# controller.net
KiCad netlist of a schematic drawn in EAGLE
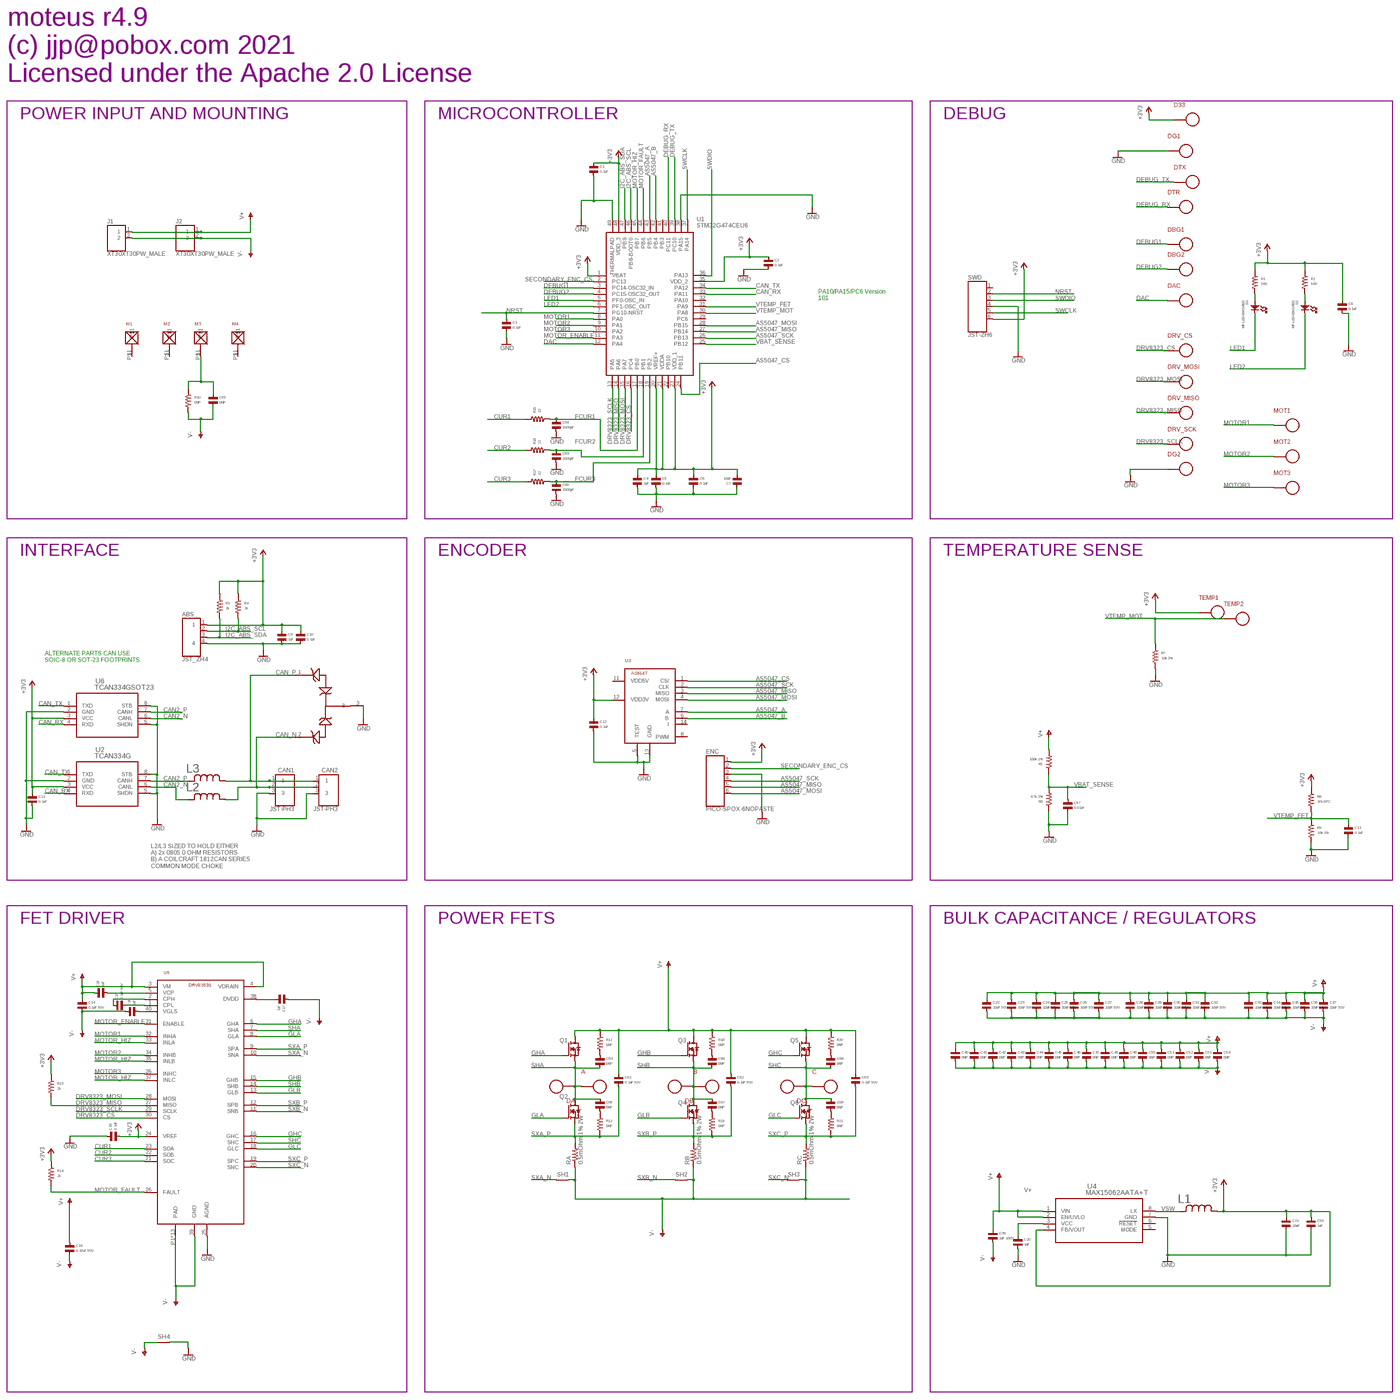
[diagram p0: schematic, sheet 1, overview]
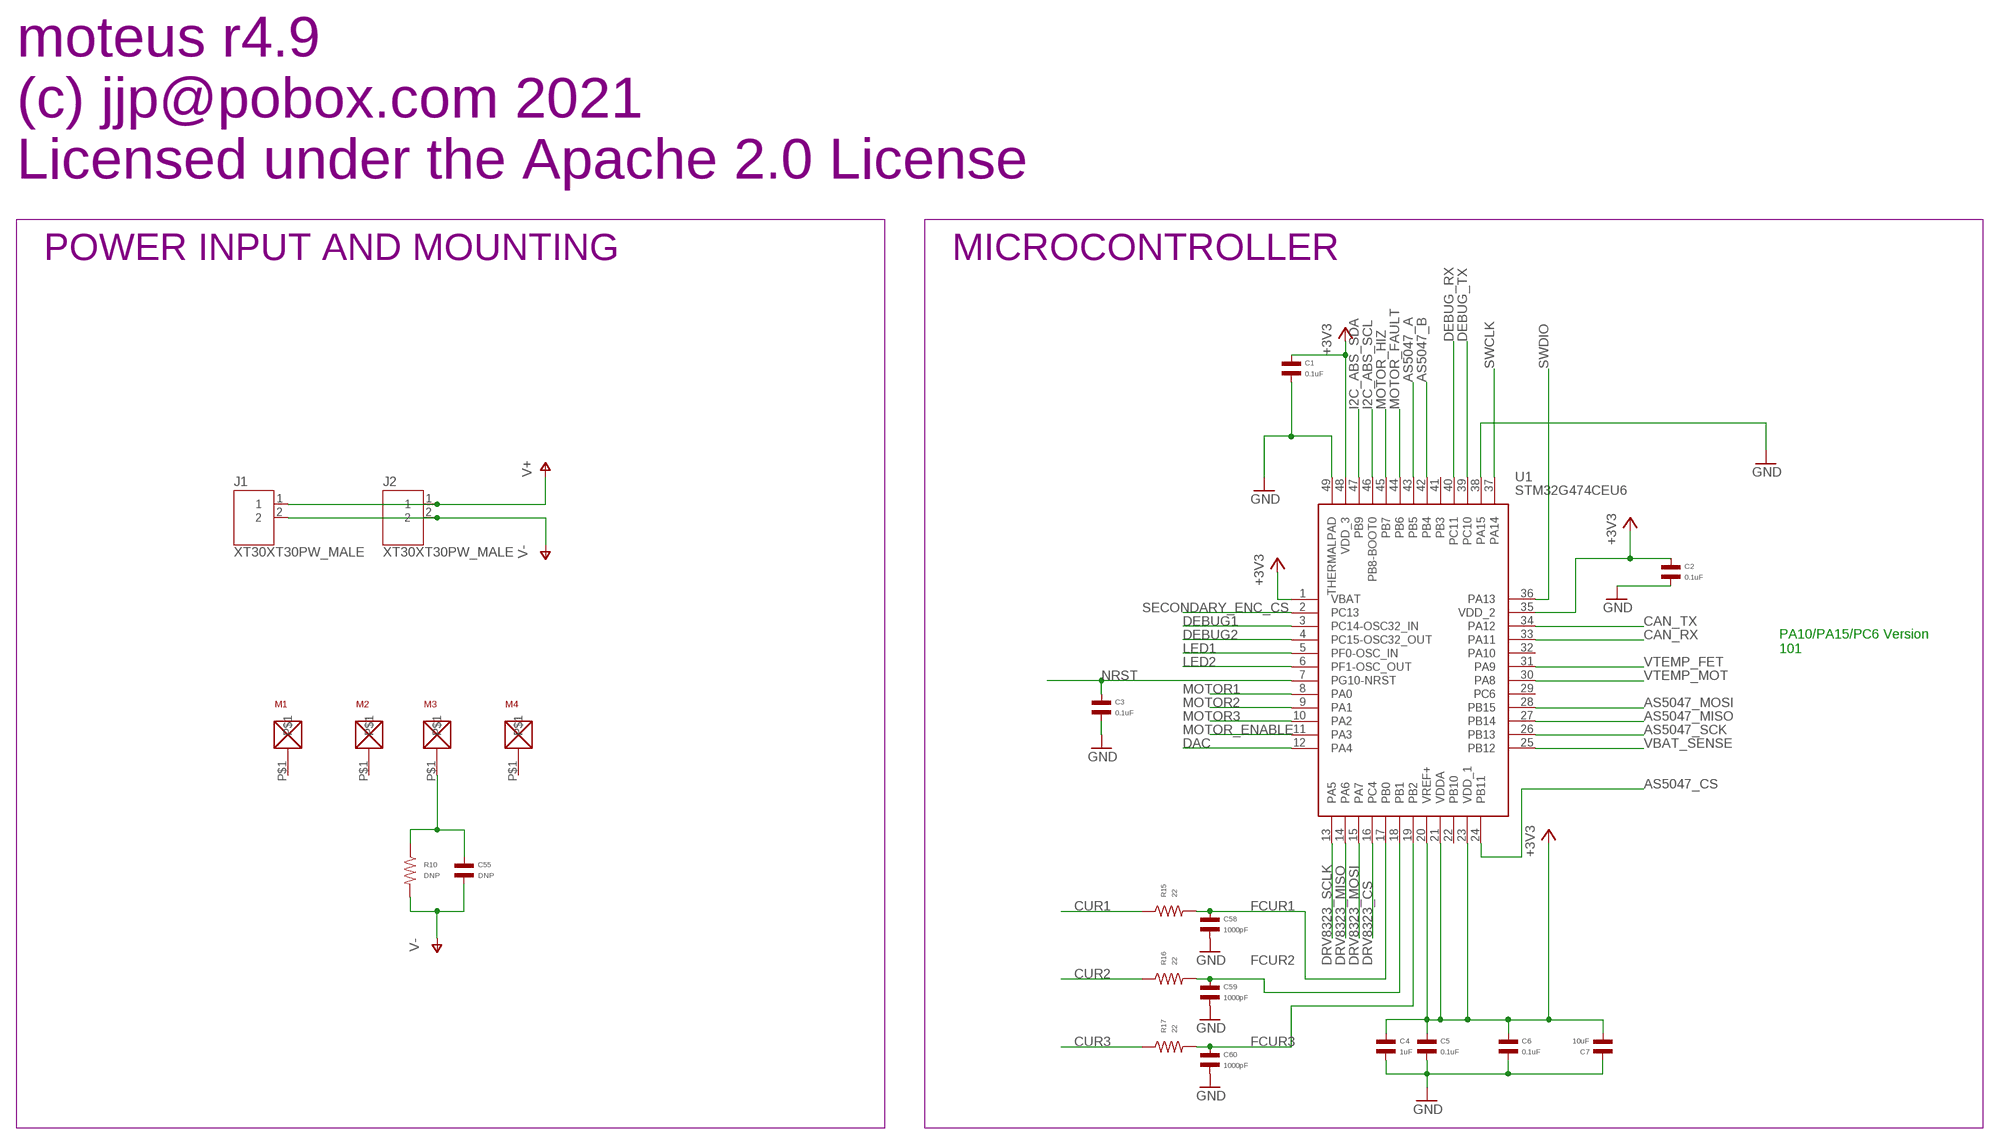
[diagram p1: schematic, sheet 1, part 1 of 4]
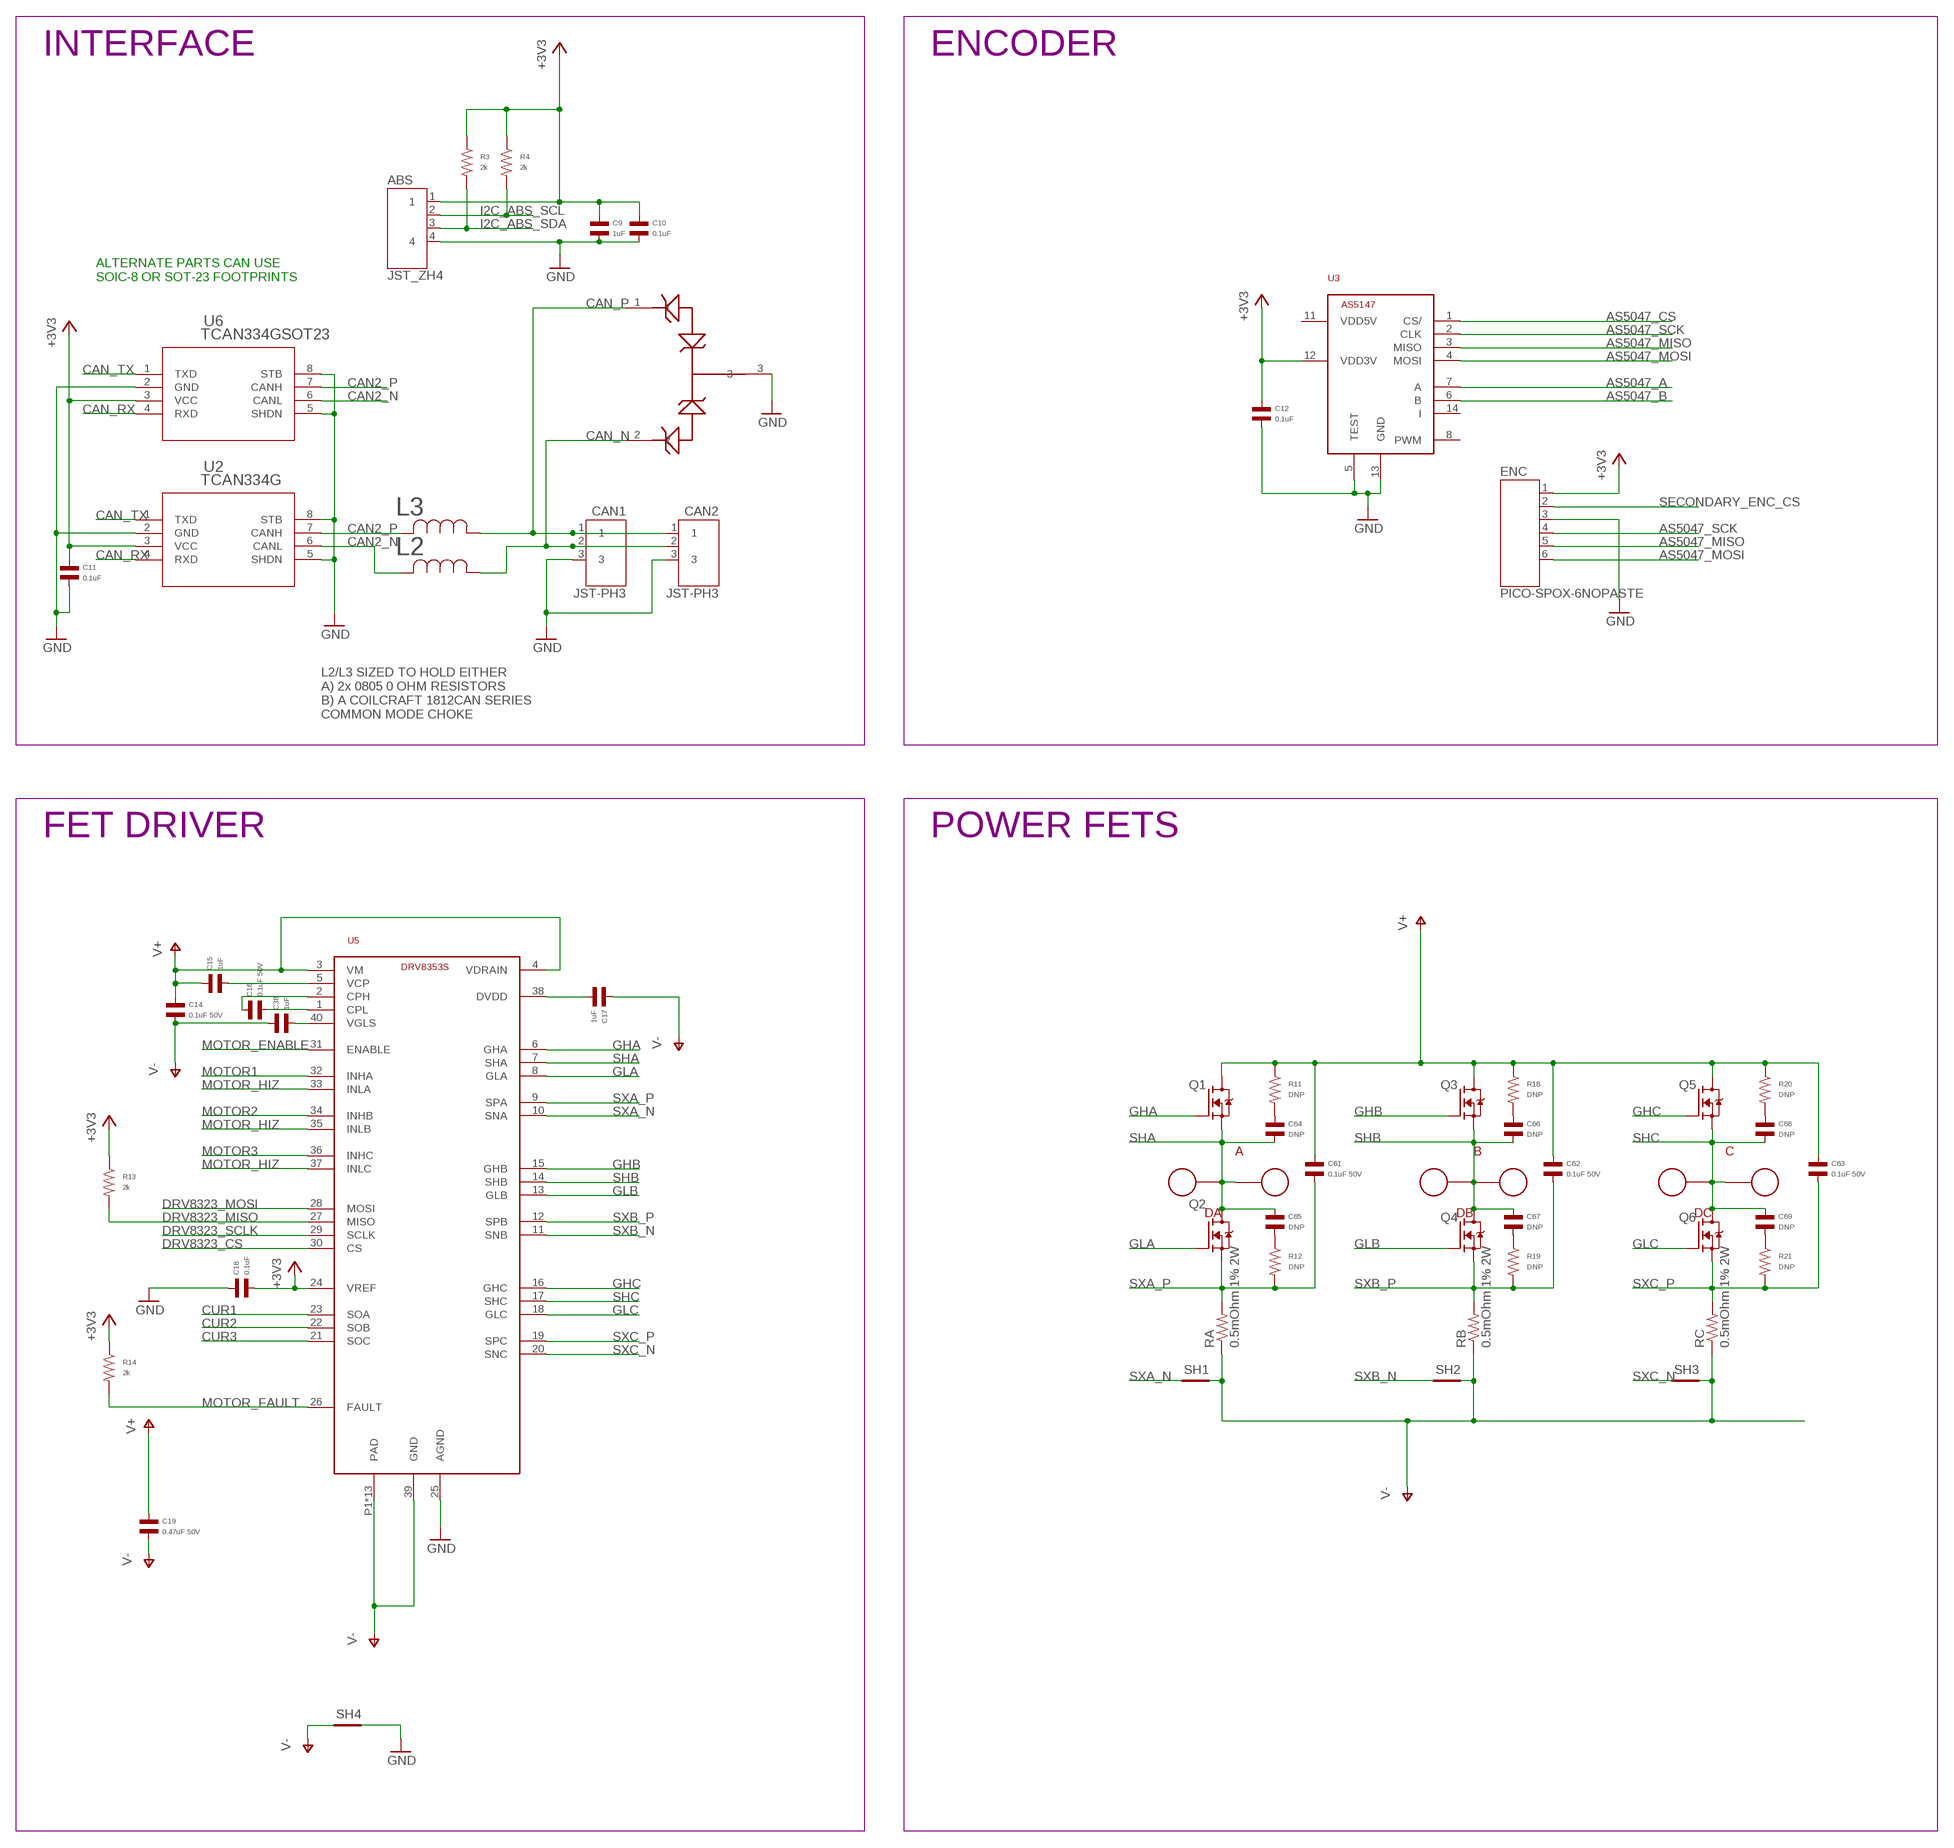
[diagram p2: schematic, sheet 1, part 2 of 4]
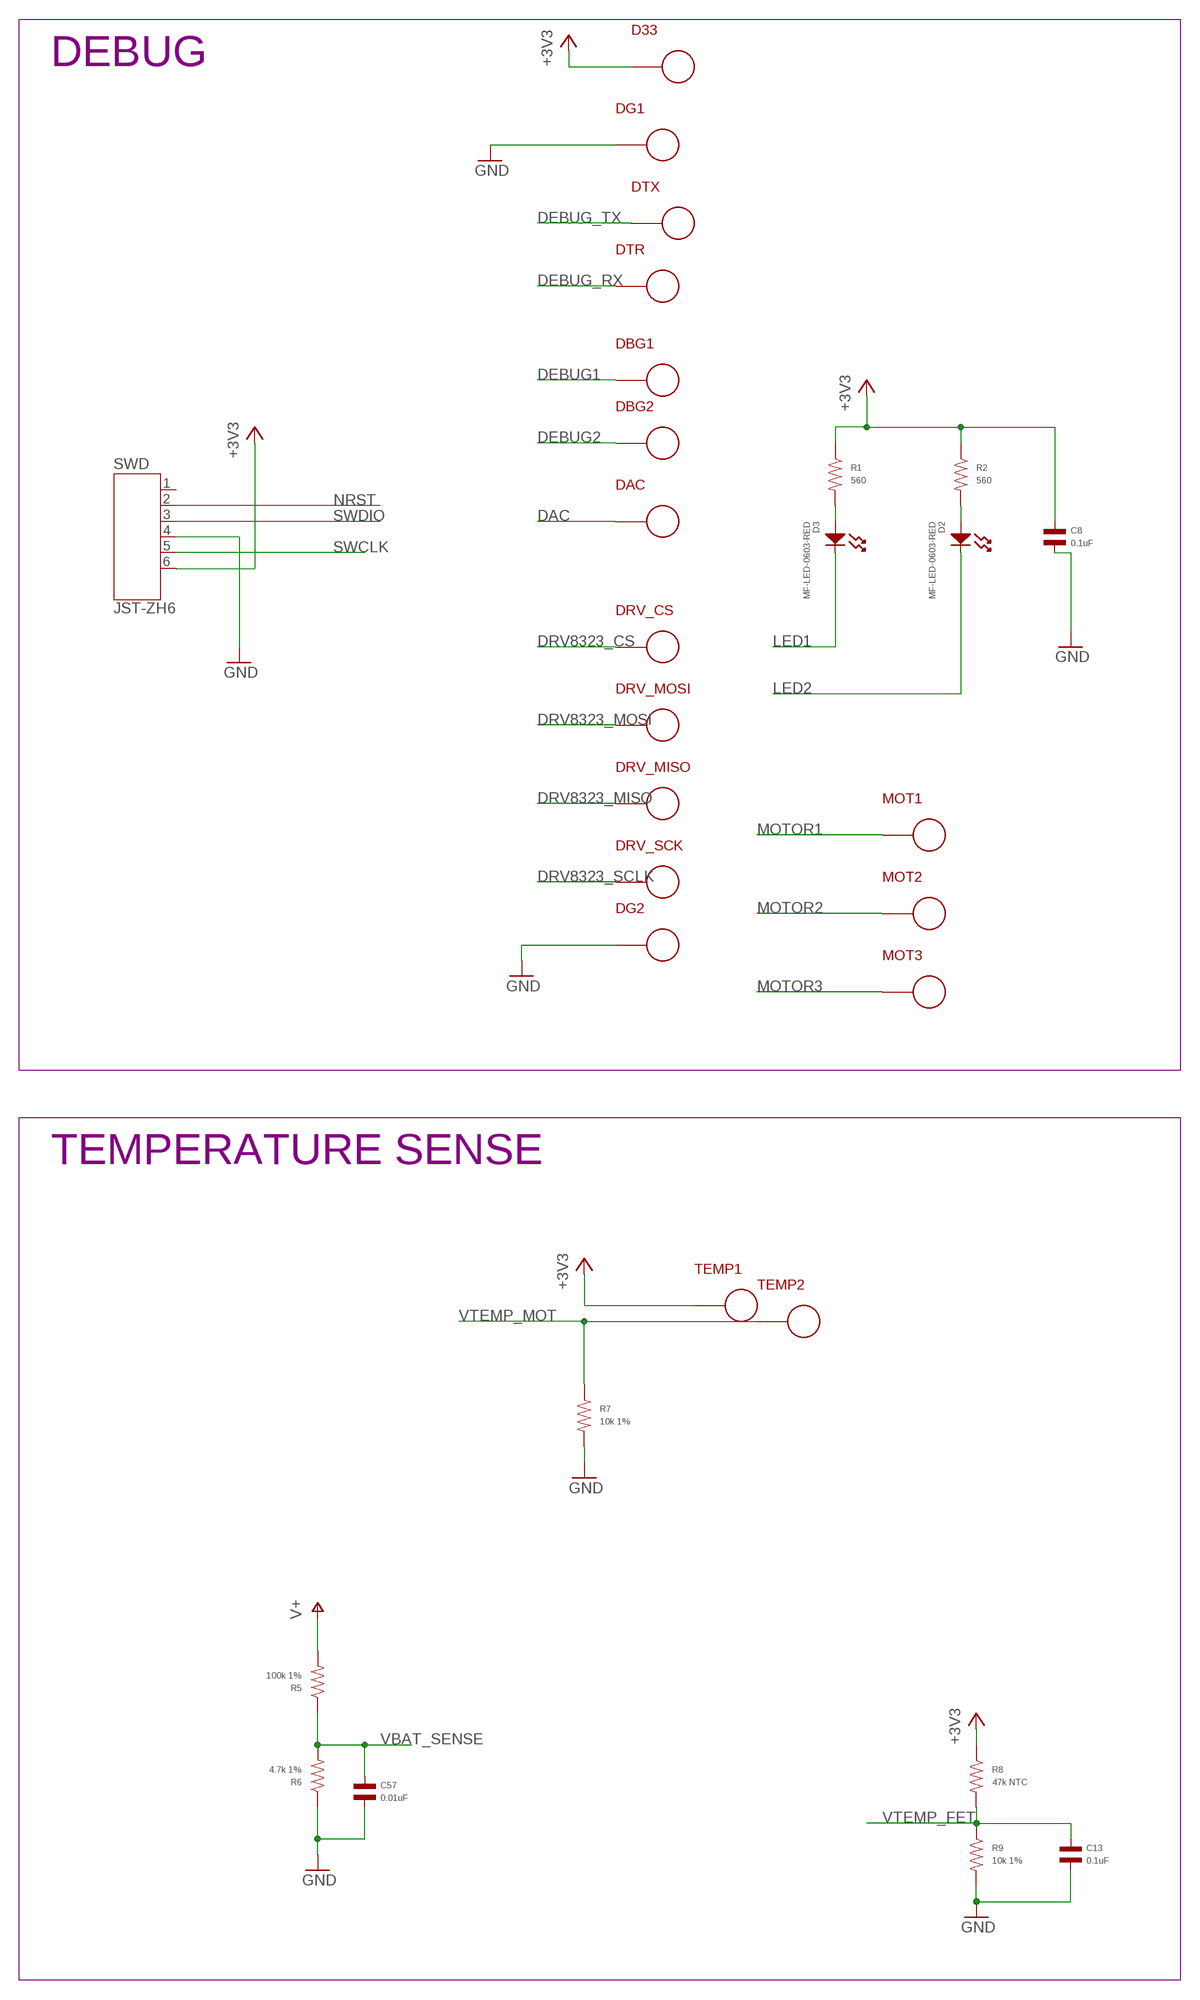
[diagram p3: schematic, sheet 1, part 3 of 4]
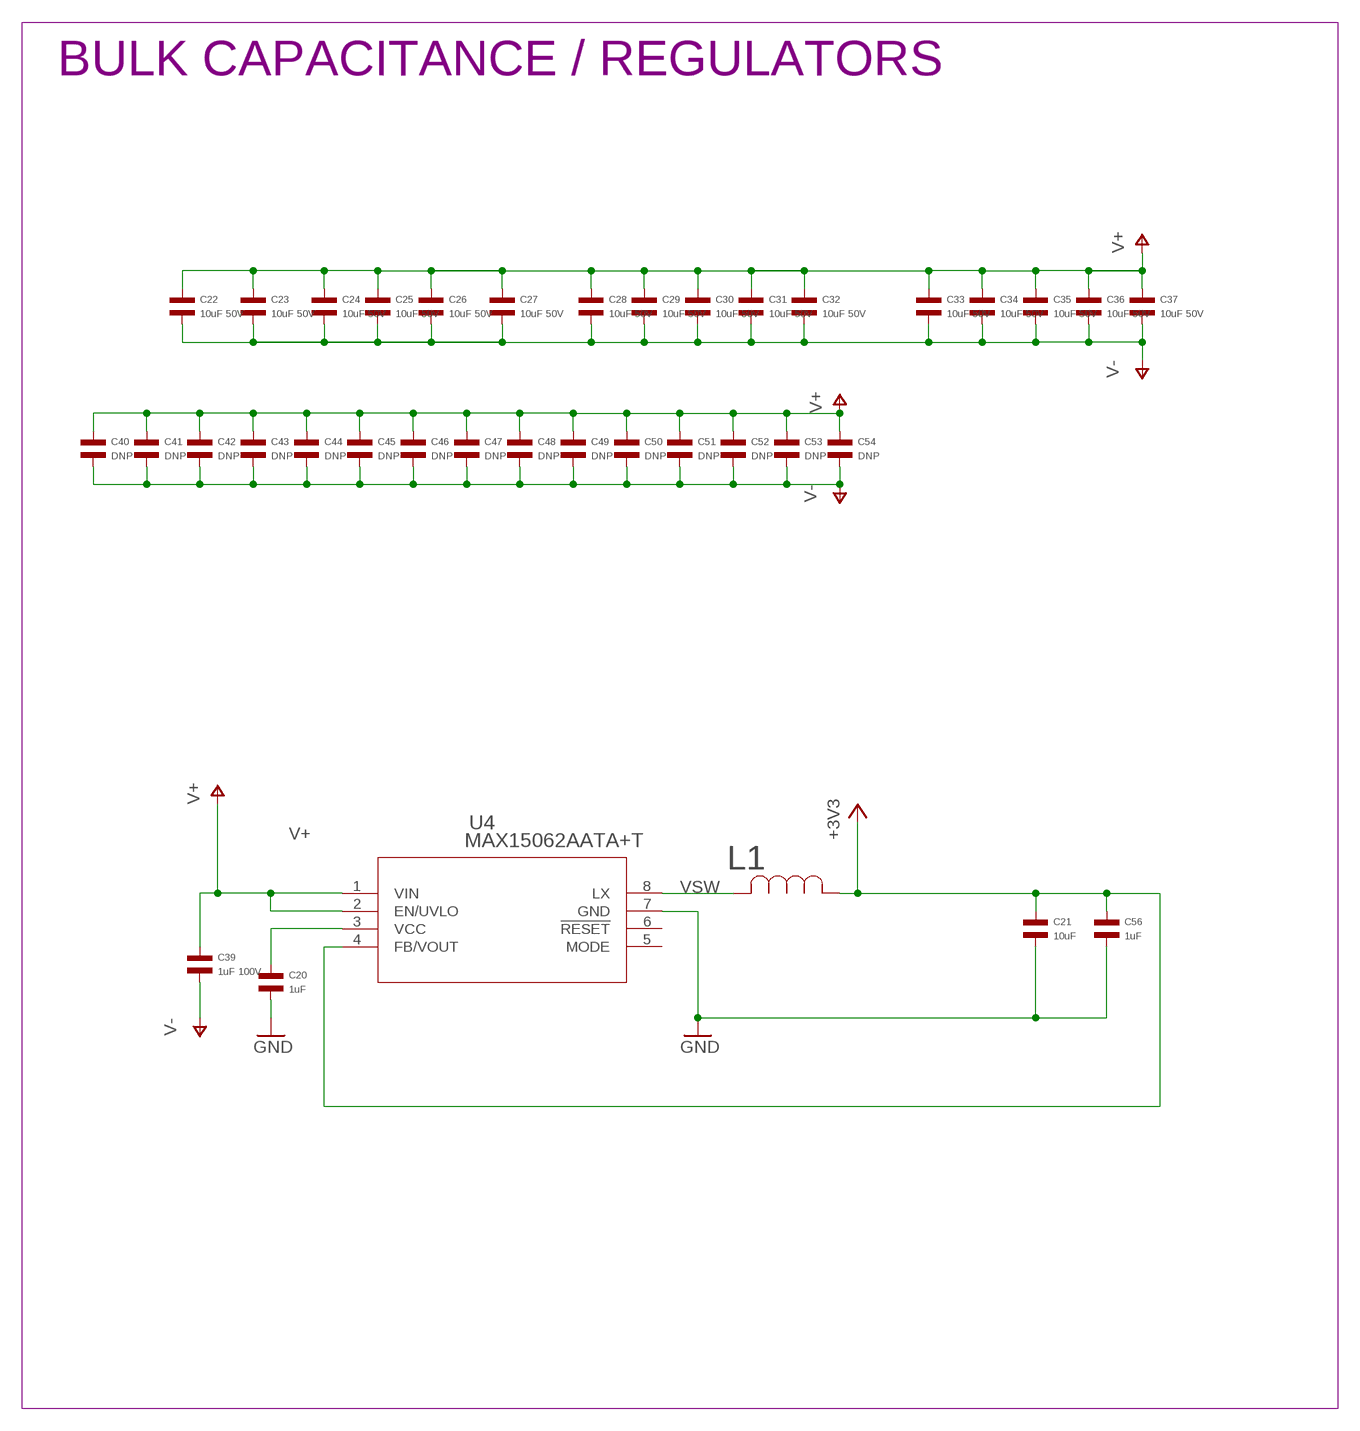
[diagram p4: schematic, sheet 1, part 4 of 4]

(export (version "E")
  (design (tool "Eeschema 10.0.6"))
  (components
    (comp (ref "A")
      (value "PAD16AWG_PAD")
      (footprint "eagle-import:16AWG_PAD")
      (libsource (lib "eagle-import") (part "PAD16AWG_PAD"))
    )
    (comp (ref "ABS")
      (value "JST_ZH4")
      (footprint "eagle-import:JST_S4B-ZR-SM4A-TF(LF)(SN)")
      (fields (field (name "MF") "JST") (field (name "MPN") "S4B-ZR-SM4A-TF(LF)(SN)"))
      (libsource (lib "eagle-import") (part "JST_ZH4"))
    )
    (comp (ref "B")
      (value "PAD16AWG_PAD")
      (footprint "eagle-import:16AWG_PAD")
      (libsource (lib "eagle-import") (part "PAD16AWG_PAD"))
    )
    (comp (ref "C")
      (value "PAD16AWG_PAD")
      (footprint "eagle-import:16AWG_PAD")
      (libsource (lib "eagle-import") (part "PAD16AWG_PAD"))
    )
    (comp (ref "C1")
      (value "0.1uF")
      (footprint "eagle-import:C0402")
      (fields (field (name "HOUSEPART") "YES") (field (name "MPN") "MF-CAP-0402-0.1uF"))
      (libsource (lib "eagle-import") (part "mfpassives_CAPACITOR_NP_0402"))
    )
    (comp (ref "C2")
      (value "0.1uF")
      (footprint "eagle-import:C0402")
      (fields (field (name "HOUSEPART") "YES") (field (name "MPN") "MF-CAP-0402-0.1uF"))
      (libsource (lib "eagle-import") (part "mfpassives_CAPACITOR_NP_0402"))
    )
    (comp (ref "C3")
      (value "0.1uF")
      (footprint "eagle-import:C0402")
      (fields (field (name "HOUSEPART") "YES") (field (name "MPN") "MF-CAP-0402-0.1uF"))
      (libsource (lib "eagle-import") (part "mfpassives_CAPACITOR_NP_0402"))
    )
    (comp (ref "C4")
      (value "1uF")
      (footprint "eagle-import:C0402")
      (fields (field (name "HOUSEPART") "YES") (field (name "MPN") "MF-CAP-0402-1uF"))
      (libsource (lib "eagle-import") (part "mfpassives_CAPACITOR_NP_0402"))
    )
    (comp (ref "C5")
      (value "0.1uF")
      (footprint "eagle-import:C0402")
      (fields (field (name "HOUSEPART") "YES") (field (name "MPN") "MF-CAP-0402-0.1uF"))
      (libsource (lib "eagle-import") (part "mfpassives_CAPACITOR_NP_0402"))
    )
    (comp (ref "C6")
      (value "0.1uF")
      (footprint "eagle-import:C0402")
      (fields (field (name "HOUSEPART") "YES") (field (name "MPN") "MF-CAP-0402-0.1uF"))
      (libsource (lib "eagle-import") (part "mfpassives_CAPACITOR_NP_0402"))
    )
    (comp (ref "C7")
      (value "10uF")
      (footprint "eagle-import:C1206")
      (fields (field (name "HOUSEPART") "YES") (field (name "MPN") "MF-CAP-1206-10uF"))
      (libsource (lib "eagle-import") (part "mfpassives_CAPACITOR_NP_1206"))
    )
    (comp (ref "C8")
      (value "0.1uF")
      (footprint "eagle-import:C0402")
      (fields (field (name "HOUSEPART") "YES") (field (name "MPN") "MF-CAP-0402-0.1uF"))
      (libsource (lib "eagle-import") (part "mfpassives_CAPACITOR_NP_0402"))
    )
    (comp (ref "C9")
      (value "1uF")
      (footprint "eagle-import:C0402")
      (fields (field (name "HOUSEPART") "YES") (field (name "MPN") "MF-CAP-0402-1uF"))
      (libsource (lib "eagle-import") (part "mfpassives_CAPACITOR_NP_0402"))
    )
    (comp (ref "C10")
      (value "0.1uF")
      (footprint "eagle-import:C0402")
      (fields (field (name "HOUSEPART") "YES") (field (name "MPN") "MF-CAP-0402-0.1uF"))
      (libsource (lib "eagle-import") (part "mfpassives_CAPACITOR_NP_0402"))
    )
    (comp (ref "C11")
      (value "0.1uF")
      (footprint "eagle-import:C0402_NOBORDER")
      (fields (field (name "HOUSEPART") "YES") (field (name "MPN") "MF-CAP-0402-0.1uF"))
      (libsource (lib "eagle-import") (part "CAPACITOR_NP_0402_NOBORDER"))
    )
    (comp (ref "C12")
      (value "0.1uF")
      (footprint "eagle-import:C0402")
      (fields (field (name "HOUSEPART") "YES") (field (name "MPN") "MF-CAP-0402-0.1uF"))
      (libsource (lib "eagle-import") (part "mfpassives_CAPACITOR_NP_0402"))
    )
    (comp (ref "C13")
      (value "0.1uF")
      (footprint "eagle-import:C0402")
      (fields (field (name "HOUSEPART") "YES") (field (name "MPN") "MF-CAP-0402-0.1uF"))
      (libsource (lib "eagle-import") (part "mfpassives_CAPACITOR_NP_0402"))
    )
    (comp (ref "C14")
      (value "0.1uF 50V")
      (footprint "eagle-import:C0402")
      (fields (field (name "MF") "TDK") (field (name "MPN") "CGA2B3X7R1H104K050BB"))
      (libsource (lib "eagle-import") (part "mfpassives_CAPACITOR_NP_0402"))
    )
    (comp (ref "C15")
      (value "1uF")
      (footprint "eagle-import:C0402")
      (fields (field (name "HOUSEPART") "YES") (field (name "MPN") "MF-CAP-0402-1uF"))
      (libsource (lib "eagle-import") (part "mfpassives_CAPACITOR_NP_0402"))
    )
    (comp (ref "C16")
      (value "0.1uF 50V")
      (footprint "eagle-import:C0402")
      (fields (field (name "MF") "TDK") (field (name "MPN") "CGA2B3X7R1H104K050BB"))
      (libsource (lib "eagle-import") (part "mfpassives_CAPACITOR_NP_0402"))
    )
    (comp (ref "C17")
      (value "1uF")
      (footprint "eagle-import:C0402")
      (fields (field (name "HOUSEPART") "YES") (field (name "MPN") "MF-CAP-0402-1uF"))
      (libsource (lib "eagle-import") (part "mfpassives_CAPACITOR_NP_0402"))
    )
    (comp (ref "C18")
      (value "0.1uF")
      (footprint "eagle-import:C0402")
      (fields (field (name "HOUSEPART") "YES") (field (name "MPN") "MF-CAP-0402-0.1uF"))
      (libsource (lib "eagle-import") (part "mfpassives_CAPACITOR_NP_0402"))
    )
    (comp (ref "C19")
      (value "0.47uF 50V")
      (footprint "eagle-import:C0402")
      (fields (field (name "MF") "Murata") (field (name "MPN") "GRM155R61H474KE11D"))
      (libsource (lib "eagle-import") (part "mfpassives_CAPACITOR_NP_0402"))
    )
    (comp (ref "C20")
      (value "1uF")
      (footprint "eagle-import:C0603")
      (fields (field (name "HOUSEPART") "1") (field (name "MPN") "MF-CAP-0603-1uF"))
      (libsource (lib "eagle-import") (part "mfpassives_CAPACITOR_NP_0603"))
    )
    (comp (ref "C21")
      (value "10uF")
      (footprint "eagle-import:C1206")
      (fields (field (name "HOUSEPART") "1") (field (name "MPN") "MF-CAP-1206-10uF"))
      (libsource (lib "eagle-import") (part "mfpassives_CAPACITOR_NP_1206"))
    )
    (comp (ref "C22")
      (value "10uF 50V")
      (footprint "eagle-import:C1206")
      (fields (field (name "MF") "TDK") (field (name "MPN") "C3216X7R1H106K160AE"))
      (libsource (lib "eagle-import") (part "mfpassives_CAPACITOR_NP_1206"))
    )
    (comp (ref "C23")
      (value "10uF 50V")
      (footprint "eagle-import:C1206")
      (fields (field (name "MF") "TDK") (field (name "MPN") "C3216X7R1H106K160AE"))
      (libsource (lib "eagle-import") (part "mfpassives_CAPACITOR_NP_1206"))
    )
    (comp (ref "C24")
      (value "10uF 50V")
      (footprint "eagle-import:C1206")
      (fields (field (name "MF") "TDK") (field (name "MPN") "C3216X7R1H106K160AE"))
      (libsource (lib "eagle-import") (part "mfpassives_CAPACITOR_NP_1206"))
    )
    (comp (ref "C25")
      (value "10uF 50V")
      (footprint "eagle-import:C1206")
      (fields (field (name "MF") "TDK") (field (name "MPN") "C3216X7R1H106K160AE"))
      (libsource (lib "eagle-import") (part "mfpassives_CAPACITOR_NP_1206"))
    )
    (comp (ref "C26")
      (value "10uF 50V")
      (footprint "eagle-import:C1206")
      (fields (field (name "MF") "TDK") (field (name "MPN") "C3216X7R1H106K160AE"))
      (libsource (lib "eagle-import") (part "mfpassives_CAPACITOR_NP_1206"))
    )
    (comp (ref "C27")
      (value "10uF 50V")
      (footprint "eagle-import:C1206")
      (fields (field (name "MF") "TDK") (field (name "MPN") "C3216X7R1H106K160AE"))
      (libsource (lib "eagle-import") (part "mfpassives_CAPACITOR_NP_1206"))
    )
    (comp (ref "C28")
      (value "10uF 50V")
      (footprint "eagle-import:C1206")
      (fields (field (name "MF") "TDK") (field (name "MPN") "C3216X7R1H106K160AE"))
      (libsource (lib "eagle-import") (part "mfpassives_CAPACITOR_NP_1206"))
    )
    (comp (ref "C29")
      (value "10uF 50V")
      (footprint "eagle-import:C1206")
      (fields (field (name "MF") "TDK") (field (name "MPN") "C3216X7R1H106K160AE"))
      (libsource (lib "eagle-import") (part "mfpassives_CAPACITOR_NP_1206"))
    )
    (comp (ref "C30")
      (value "10uF 50V")
      (footprint "eagle-import:C1206")
      (fields (field (name "MF") "TDK") (field (name "MPN") "C3216X7R1H106K160AE"))
      (libsource (lib "eagle-import") (part "mfpassives_CAPACITOR_NP_1206"))
    )
    (comp (ref "C31")
      (value "10uF 50V")
      (footprint "eagle-import:C1206")
      (fields (field (name "MF") "TDK") (field (name "MPN") "C3216X7R1H106K160AE"))
      (libsource (lib "eagle-import") (part "mfpassives_CAPACITOR_NP_1206"))
    )
    (comp (ref "C32")
      (value "10uF 50V")
      (footprint "eagle-import:C1206")
      (fields (field (name "MF") "TDK") (field (name "MPN") "C3216X7R1H106K160AE"))
      (libsource (lib "eagle-import") (part "mfpassives_CAPACITOR_NP_1206"))
    )
    (comp (ref "C33")
      (value "10uF 50V")
      (footprint "eagle-import:C1206")
      (fields (field (name "MF") "TDK") (field (name "MPN") "C3216X7R1H106K160AE"))
      (libsource (lib "eagle-import") (part "mfpassives_CAPACITOR_NP_1206"))
    )
    (comp (ref "C34")
      (value "10uF 50V")
      (footprint "eagle-import:C1206")
      (fields (field (name "MF") "TDK") (field (name "MPN") "C3216X7R1H106K160AE"))
      (libsource (lib "eagle-import") (part "mfpassives_CAPACITOR_NP_1206"))
    )
    (comp (ref "C35")
      (value "10uF 50V")
      (footprint "eagle-import:C1206_NOBORDER")
      (fields (field (name "MF") "TDK") (field (name "MPN") "C3216X7R1H106K160AE"))
      (libsource (lib "eagle-import") (part "CAPACITOR_NP_1206_NOBORDER"))
    )
    (comp (ref "C36")
      (value "10uF 50V")
      (footprint "eagle-import:C1206")
      (fields (field (name "MF") "TDK") (field (name "MPN") "C3216X7R1H106K160AE"))
      (libsource (lib "eagle-import") (part "mfpassives_CAPACITOR_NP_1206"))
    )
    (comp (ref "C37")
      (value "10uF 50V")
      (footprint "eagle-import:C1206")
      (fields (field (name "MF") "TDK") (field (name "MPN") "C3216X7R1H106K160AE"))
      (libsource (lib "eagle-import") (part "mfpassives_CAPACITOR_NP_1206"))
    )
    (comp (ref "C38")
      (value "1uF")
      (footprint "eagle-import:C0603")
      (fields
        (field (name "HOUSEPART") "YES")
        (field (name "MF") "TDK")
        (field (name "MPN") "C1608X7R1E105K080AE")
      )
      (libsource (lib "eagle-import") (part "mfpassives_CAPACITOR_NP_0603"))
    )
    (comp (ref "C39")
      (value "1uF 100V")
      (footprint "eagle-import:C0805")
      (fields (field (name "MF") "MURATA") (field (name "MPN") "GCM21BC72A105KE36L"))
      (libsource (lib "eagle-import") (part "mfpassives_CAPACITOR_NP_0805"))
    )
    (comp (ref "C40")
      (value "DNP")
      (footprint "eagle-import:C1206_NOCREAM")
      (libsource (lib "eagle-import") (part "CAPACITOR_NP_1206_NOCREAM"))
    )
    (comp (ref "C41")
      (value "DNP")
      (footprint "eagle-import:C1206_NOCREAM")
      (libsource (lib "eagle-import") (part "CAPACITOR_NP_1206_NOCREAM"))
    )
    (comp (ref "C42")
      (value "DNP")
      (footprint "eagle-import:C1206_NOCREAM")
      (libsource (lib "eagle-import") (part "CAPACITOR_NP_1206_NOCREAM"))
    )
    (comp (ref "C43")
      (value "DNP")
      (footprint "eagle-import:C1206_NOCREAM")
      (libsource (lib "eagle-import") (part "CAPACITOR_NP_1206_NOCREAM"))
    )
    (comp (ref "C44")
      (value "DNP")
      (footprint "eagle-import:C1206_NOCREAM")
      (libsource (lib "eagle-import") (part "CAPACITOR_NP_1206_NOCREAM"))
    )
    (comp (ref "C45")
      (value "DNP")
      (footprint "eagle-import:C1206_NOCREAM")
      (libsource (lib "eagle-import") (part "CAPACITOR_NP_1206_NOCREAM"))
    )
    (comp (ref "C46")
      (value "DNP")
      (footprint "eagle-import:C1206_NOCREAM")
      (libsource (lib "eagle-import") (part "CAPACITOR_NP_1206_NOCREAM"))
    )
    (comp (ref "C47")
      (value "DNP")
      (footprint "eagle-import:C1206_NOCREAM")
      (libsource (lib "eagle-import") (part "CAPACITOR_NP_1206_NOCREAM"))
    )
    (comp (ref "C48")
      (value "DNP")
      (footprint "eagle-import:C1206_NOCREAM")
      (libsource (lib "eagle-import") (part "CAPACITOR_NP_1206_NOCREAM"))
    )
    (comp (ref "C49")
      (value "DNP")
      (footprint "eagle-import:C1206_NOCREAM")
      (libsource (lib "eagle-import") (part "CAPACITOR_NP_1206_NOCREAM"))
    )
    (comp (ref "C50")
      (value "DNP")
      (footprint "eagle-import:C1206_NOCREAM")
      (libsource (lib "eagle-import") (part "CAPACITOR_NP_1206_NOCREAM"))
    )
    (comp (ref "C51")
      (value "DNP")
      (footprint "eagle-import:C1206_NOCREAM")
      (libsource (lib "eagle-import") (part "CAPACITOR_NP_1206_NOCREAM"))
    )
    (comp (ref "C52")
      (value "DNP")
      (footprint "eagle-import:C1206_NOCREAM")
      (libsource (lib "eagle-import") (part "CAPACITOR_NP_1206_NOCREAM"))
    )
    (comp (ref "C53")
      (value "DNP")
      (footprint "eagle-import:C1206_NOCREAM")
      (libsource (lib "eagle-import") (part "CAPACITOR_NP_1206_NOCREAM"))
    )
    (comp (ref "C54")
      (value "DNP")
      (footprint "eagle-import:C1206_NOCREAM")
      (libsource (lib "eagle-import") (part "CAPACITOR_NP_1206_NOCREAM"))
    )
    (comp (ref "C55")
      (value "DNP")
      (footprint "eagle-import:C0402")
      (fields (field (name "POPULATE") "0"))
      (libsource (lib "eagle-import") (part "mfpassives_CAPACITOR_NP_0402"))
    )
    (comp (ref "C56")
      (value "1uF")
      (footprint "eagle-import:C0402")
      (fields (field (name "HOUSEPART") "YES") (field (name "MPN") "MF-CAP-0402-1uF"))
      (libsource (lib "eagle-import") (part "mfpassives_CAPACITOR_NP_0402"))
    )
    (comp (ref "C57")
      (value "0.01uF")
      (footprint "eagle-import:C0402")
      (fields (field (name "HOUSEPART") "YES") (field (name "MPN") "MF-CAP-0402-0.01uF"))
      (libsource (lib "eagle-import") (part "mfpassives_CAPACITOR_NP_0402"))
    )
    (comp (ref "C58")
      (value "1000pF")
      (footprint "eagle-import:C0402_NOBORDER")
      (fields (field (name "HOUSEPART") "1") (field (name "MPN") "MF-CAP-0402-1nF"))
      (libsource (lib "eagle-import") (part "CAPACITOR_NP_0402_NOBORDER"))
    )
    (comp (ref "C59")
      (value "1000pF")
      (footprint "eagle-import:C0402_NOBORDER")
      (fields (field (name "HOUSEPART") "1") (field (name "MPN") "MF-CAP-0402-1nF"))
      (libsource (lib "eagle-import") (part "CAPACITOR_NP_0402_NOBORDER"))
    )
    (comp (ref "C60")
      (value "1000pF")
      (footprint "eagle-import:C0402_NOBORDER")
      (fields (field (name "HOUSEPART") "1") (field (name "MPN") "MF-CAP-0402-1nF"))
      (libsource (lib "eagle-import") (part "CAPACITOR_NP_0402_NOBORDER"))
    )
    (comp (ref "C61")
      (value "0.1uF 50V")
      (footprint "eagle-import:C1206")
      (fields (field (name "MF") "KYOCERA AVX") (field (name "MPN") "12065C104KAZ2A"))
      (libsource (lib "eagle-import") (part "mfpassives_CAPACITOR_NP_1206"))
    )
    (comp (ref "C62")
      (value "0.1uF 50V")
      (footprint "eagle-import:C0603_NOBORDER")
      (fields (field (name "MF") "KYOCERA AVX") (field (name "MPN") "06035C104KAZ2A"))
      (libsource (lib "eagle-import") (part "CAPACITOR_NP_0603_NOBORDER"))
    )
    (comp (ref "C63")
      (value "0.1uF 50V")
      (footprint "eagle-import:C1206")
      (fields (field (name "MF") "KYOCERA AVX") (field (name "MPN") "12065C104KAZ2A"))
      (libsource (lib "eagle-import") (part "mfpassives_CAPACITOR_NP_1206"))
    )
    (comp (ref "C64")
      (value "DNP")
      (footprint "eagle-import:C0603")
      (fields (field (name "POPULATE") "0"))
      (libsource (lib "eagle-import") (part "mfpassives_CAPACITOR_NP_0603"))
    )
    (comp (ref "C65")
      (value "DNP")
      (footprint "eagle-import:C0603")
      (fields (field (name "POPULATE") "0"))
      (libsource (lib "eagle-import") (part "mfpassives_CAPACITOR_NP_0603"))
    )
    (comp (ref "C66")
      (value "DNP")
      (footprint "eagle-import:C0603")
      (fields (field (name "POPULATE") "0"))
      (libsource (lib "eagle-import") (part "mfpassives_CAPACITOR_NP_0603"))
    )
    (comp (ref "C67")
      (value "DNP")
      (footprint "eagle-import:C0603")
      (fields (field (name "POPULATE") "0"))
      (libsource (lib "eagle-import") (part "mfpassives_CAPACITOR_NP_0603"))
    )
    (comp (ref "C68")
      (value "DNP")
      (footprint "eagle-import:C0603")
      (fields (field (name "POPULATE") "0"))
      (libsource (lib "eagle-import") (part "mfpassives_CAPACITOR_NP_0603"))
    )
    (comp (ref "C69")
      (value "DNP")
      (footprint "eagle-import:C0603")
      (fields (field (name "POPULATE") "0"))
      (libsource (lib "eagle-import") (part "mfpassives_CAPACITOR_NP_0603"))
    )
    (comp (ref "CAN1")
      (value "JST-PH3")
      (footprint "eagle-import:JST_S3B-PH-SM4-TB(LF)(SN)")
      (fields (field (name "MF") "JST") (field (name "MPN") "S3B-PH-SM4-TB(LF)(SN)"))
      (libsource (lib "eagle-import") (part "JST-PH3"))
    )
    (comp (ref "CAN2")
      (value "JST-PH3")
      (footprint "eagle-import:JST_S3B-PH-SM4-TB(LF)(SN)")
      (fields (field (name "MF") "JST") (field (name "MPN") "S3B-PH-SM4-TB(LF)(SN)"))
      (libsource (lib "eagle-import") (part "JST-PH3"))
    )
    (comp (ref "D2")
      (value "MF-LED-0603-RED")
      (footprint "eagle-import:LED0603")
      (fields (field (name "HOUSEPART") "YES") (field (name "MPN") "MF-LED-0603-GREEN"))
      (libsource (lib "eagle-import") (part "LED_SINGLE-0603-RED"))
    )
    (comp (ref "D3")
      (value "MF-LED-0603-RED")
      (footprint "eagle-import:LED0603")
      (fields (field (name "HOUSEPART") "YES"))
      (libsource (lib "eagle-import") (part "LED_SINGLE-0603-RED"))
    )
    (comp (ref "D4")
      (value "DUAL_TVS")
      (footprint "eagle-import:SOT23-3")
      (fields (field (name "MPN") "CDSOT23-0502B"))
      (libsource (lib "eagle-import") (part "DUAL_TVS"))
    )
    (comp (ref "D33")
      (value "PAD24AWG_PAD")
      (footprint "eagle-import:24AWG_PAD")
      (libsource (lib "eagle-import") (part "PAD24AWG_PAD"))
    )
    (comp (ref "DA")
      (value "PAD24AWG_PAD")
      (footprint "eagle-import:24AWG_PAD")
      (libsource (lib "eagle-import") (part "PAD24AWG_PAD"))
    )
    (comp (ref "DAC")
      (value "PAD24AWG_PAD")
      (footprint "eagle-import:24AWG_PAD")
      (libsource (lib "eagle-import") (part "PAD24AWG_PAD"))
    )
    (comp (ref "DB")
      (value "PAD24AWG_PAD")
      (footprint "eagle-import:24AWG_PAD")
      (libsource (lib "eagle-import") (part "PAD24AWG_PAD"))
    )
    (comp (ref "DBG1")
      (value "PAD24AWG_PAD")
      (footprint "eagle-import:24AWG_PAD")
      (libsource (lib "eagle-import") (part "PAD24AWG_PAD"))
    )
    (comp (ref "DBG2")
      (value "PAD24AWG_PAD")
      (footprint "eagle-import:24AWG_PAD")
      (libsource (lib "eagle-import") (part "PAD24AWG_PAD"))
    )
    (comp (ref "DC")
      (value "PAD24AWG_PAD")
      (footprint "eagle-import:24AWG_PAD")
      (libsource (lib "eagle-import") (part "PAD24AWG_PAD"))
    )
    (comp (ref "DG1")
      (value "PAD24AWG_PAD")
      (footprint "eagle-import:24AWG_PAD")
      (libsource (lib "eagle-import") (part "PAD24AWG_PAD"))
    )
    (comp (ref "DG2")
      (value "PAD24AWG_PAD")
      (footprint "eagle-import:24AWG_PAD")
      (libsource (lib "eagle-import") (part "PAD24AWG_PAD"))
    )
    (comp (ref "DRV_CS")
      (value "PAD24AWG_PAD")
      (footprint "eagle-import:24AWG_PAD")
      (libsource (lib "eagle-import") (part "PAD24AWG_PAD"))
    )
    (comp (ref "DRV_MISO")
      (value "PAD24AWG_PAD")
      (footprint "eagle-import:24AWG_PAD")
      (libsource (lib "eagle-import") (part "PAD24AWG_PAD"))
    )
    (comp (ref "DRV_MOSI")
      (value "PAD24AWG_PAD")
      (footprint "eagle-import:24AWG_PAD")
      (libsource (lib "eagle-import") (part "PAD24AWG_PAD"))
    )
    (comp (ref "DRV_SCK")
      (value "PAD24AWG_PAD")
      (footprint "eagle-import:24AWG_PAD")
      (libsource (lib "eagle-import") (part "PAD24AWG_PAD"))
    )
    (comp (ref "DTR")
      (value "PAD24AWG_PAD")
      (footprint "eagle-import:24AWG_PAD")
      (libsource (lib "eagle-import") (part "PAD24AWG_PAD"))
    )
    (comp (ref "DTX")
      (value "PAD24AWG_PAD")
      (footprint "eagle-import:24AWG_PAD")
      (libsource (lib "eagle-import") (part "PAD24AWG_PAD"))
    )
    (comp (ref "ENC")
      (value "PICO-SPOX-6NOPASTE")
      (footprint "eagle-import:PICO-SPOX-SMT-RA-6-NOPASTE")
      (libsource (lib "eagle-import") (part "PICO-SPOX-6NOPASTE"))
    )
    (comp (ref "J1")
      (value "XT30XT30PW_MALE")
      (footprint "eagle-import:XT30PW_MALE")
      (libsource (lib "eagle-import") (part "XT30XT30PW_MALE"))
    )
    (comp (ref "J2")
      (value "XT30XT30PW_MALE")
      (footprint "eagle-import:XT30PW_MALE")
      (libsource (lib "eagle-import") (part "XT30XT30PW_MALE"))
    )
    (comp (ref "L1")
      (value "SRN4018-220M")
      (footprint "eagle-import:IND_BOURNS_SRN4018")
      (fields
        (field (name "MANUFACTURER_PART_NUMBER") "SRN4018220M")
        (field (name "MANUFACTURER_PART_NUMBER_1") "SRN4018-330M")
        (field (name "MPN") "SRN4018-330M")
      )
      (libsource (lib "eagle-import") (part "SRN4018-220M"))
    )
    (comp (ref "L2")
      (value "HALF_CHOKE")
      (footprint "eagle-import:1812_COMMON_HALF")
      (fields (field (name "MPN") "MF-RES-0805-0"))
      (libsource (lib "eagle-import") (part "HALF_CHOKE"))
    )
    (comp (ref "L3")
      (value "HALF_CHOKE")
      (footprint "eagle-import:1812_COMMON_HALF")
      (fields (field (name "MPN") "MF-RES-0805-0"))
      (libsource (lib "eagle-import") (part "HALF_CHOKE"))
    )
    (comp (ref "M1")
      (value "MOUNT")
      (footprint "eagle-import:M2.5MOUNT")
      (libsource (lib "eagle-import") (part "MOUNT"))
    )
    (comp (ref "M2")
      (value "MOUNT")
      (footprint "eagle-import:M2.5MOUNT")
      (libsource (lib "eagle-import") (part "MOUNT"))
    )
    (comp (ref "M3")
      (value "MOUNT")
      (footprint "eagle-import:M2.5MOUNT")
      (libsource (lib "eagle-import") (part "MOUNT"))
    )
    (comp (ref "M4")
      (value "MOUNT")
      (footprint "eagle-import:M2.5MOUNT")
      (libsource (lib "eagle-import") (part "MOUNT"))
    )
    (comp (ref "MOT1")
      (value "PAD24AWG_PAD")
      (footprint "eagle-import:24AWG_PAD")
      (libsource (lib "eagle-import") (part "PAD24AWG_PAD"))
    )
    (comp (ref "MOT2")
      (value "PAD24AWG_PAD")
      (footprint "eagle-import:24AWG_PAD")
      (libsource (lib "eagle-import") (part "PAD24AWG_PAD"))
    )
    (comp (ref "MOT3")
      (value "PAD24AWG_PAD")
      (footprint "eagle-import:24AWG_PAD")
      (libsource (lib "eagle-import") (part "PAD24AWG_PAD"))
    )
    (comp (ref "Q1")
      (value "TPH1R204PLSOP_ADVANCE_8")
      (footprint "eagle-import:SOP_ADVANCE_8")
      (fields
        (field (name "MF") "Toshiba")
        (field (name "MPN") "TPH1R204PL")
        (field (name "MF_1") "Toshiba")
        (field (name "MPN_1") "TPH2R506PL,L1Q")
      )
      (libsource (lib "eagle-import") (part "TPH1R204PLSOP_ADVANCE_8"))
    )
    (comp (ref "Q2")
      (value "TPH1R204PLSOP_ADVANCE_8")
      (footprint "eagle-import:SOP_ADVANCE_8")
      (fields
        (field (name "MF") "Toshiba")
        (field (name "MPN") "TPH1R204PL")
        (field (name "MF_1") "Toshiba")
        (field (name "MPN_1") "TPH2R506PL,L1Q")
      )
      (libsource (lib "eagle-import") (part "TPH1R204PLSOP_ADVANCE_8"))
    )
    (comp (ref "Q3")
      (value "TPH1R204PLSOP_ADVANCE_8")
      (footprint "eagle-import:SOP_ADVANCE_8")
      (fields
        (field (name "MF") "Toshiba")
        (field (name "MPN") "TPH1R204PL")
        (field (name "MF_1") "Toshiba")
        (field (name "MPN_1") "TPH2R506PL,L1Q")
      )
      (libsource (lib "eagle-import") (part "TPH1R204PLSOP_ADVANCE_8"))
    )
    (comp (ref "Q4")
      (value "TPH1R204PLSOP_ADVANCE_8")
      (footprint "eagle-import:SOP_ADVANCE_8")
      (fields
        (field (name "MF") "Toshiba")
        (field (name "MPN") "TPH1R204PL")
        (field (name "MF_1") "Toshiba")
        (field (name "MPN_1") "TPH2R506PL,L1Q")
      )
      (libsource (lib "eagle-import") (part "TPH1R204PLSOP_ADVANCE_8"))
    )
    (comp (ref "Q5")
      (value "TPH1R204PLSOP_ADVANCE_8")
      (footprint "eagle-import:SOP_ADVANCE_8")
      (fields
        (field (name "MF") "Toshiba")
        (field (name "MPN") "TPH1R204PL")
        (field (name "MF_1") "Toshiba")
        (field (name "MPN_1") "TPH2R506PL,L1Q")
      )
      (libsource (lib "eagle-import") (part "TPH1R204PLSOP_ADVANCE_8"))
    )
    (comp (ref "Q6")
      (value "TPH1R204PLSOP_ADVANCE_8")
      (footprint "eagle-import:SOP_ADVANCE_8")
      (fields
        (field (name "MF") "Toshiba")
        (field (name "MPN") "TPH1R204PL")
        (field (name "MF_1") "Toshiba")
        (field (name "MPN_1") "TPH2R506PL,L1Q")
      )
      (libsource (lib "eagle-import") (part "TPH1R204PLSOP_ADVANCE_8"))
    )
    (comp (ref "R1")
      (value "560")
      (footprint "eagle-import:R0402")
      (fields (field (name "HOUSEPART") "1") (field (name "MPN") "MF-RES-0402-560"))
      (libsource (lib "eagle-import") (part "mfpassives_RESISTOR_0402"))
    )
    (comp (ref "R2")
      (value "560")
      (footprint "eagle-import:R0402")
      (fields (field (name "HOUSEPART") "1") (field (name "MPN") "MF-RES-0402-560"))
      (libsource (lib "eagle-import") (part "mfpassives_RESISTOR_0402"))
    )
    (comp (ref "R3")
      (value "2k")
      (footprint "eagle-import:R0402")
      (fields (field (name "HOUSEPART") "YES") (field (name "MPN") "MF-RES-0402-2K"))
      (libsource (lib "eagle-import") (part "mfpassives_RESISTOR_0402"))
    )
    (comp (ref "R4")
      (value "2k")
      (footprint "eagle-import:R0402")
      (fields (field (name "HOUSEPART") "YES") (field (name "MPN") "MF-RES-0402-2K"))
      (libsource (lib "eagle-import") (part "mfpassives_RESISTOR_0402"))
    )
    (comp (ref "R5")
      (value "100k 1%")
      (footprint "eagle-import:R0402")
      (fields (field (name "MF") "Yageo") (field (name "MPN") "RC0402FR-07100KL"))
      (libsource (lib "eagle-import") (part "mfpassives_RESISTOR_0402"))
    )
    (comp (ref "R6")
      (value "4.7k 1%")
      (footprint "eagle-import:R0402")
      (fields (field (name "MF") "Yageo") (field (name "MPN") "RC0402FR-074K7L"))
      (libsource (lib "eagle-import") (part "mfpassives_RESISTOR_0402"))
    )
    (comp (ref "R7")
      (value "10k 1%")
      (footprint "eagle-import:R0402")
      (fields (field (name "MF") "Yageo") (field (name "MPN") "RC0402FR-0710KL"))
      (libsource (lib "eagle-import") (part "mfpassives_RESISTOR_0402"))
    )
    (comp (ref "R8")
      (value "47k NTC")
      (footprint "eagle-import:R0402")
      (fields (field (name "MF") "Murata") (field (name "MPN") "NCP15WB473F03RC"))
      (libsource (lib "eagle-import") (part "mfpassives_RESISTOR_0402"))
    )
    (comp (ref "R9")
      (value "10k 1%")
      (footprint "eagle-import:R0402")
      (fields (field (name "MF") "Yageo") (field (name "MPN") "RC0402FR-0710KL"))
      (libsource (lib "eagle-import") (part "mfpassives_RESISTOR_0402"))
    )
    (comp (ref "R10")
      (value "DNP")
      (footprint "eagle-import:R0402")
      (fields (field (name "POPULATE") "0"))
      (libsource (lib "eagle-import") (part "mfpassives_RESISTOR_0402"))
    )
    (comp (ref "R11")
      (value "DNP")
      (footprint "eagle-import:R0603")
      (fields (field (name "POPULATE") "0"))
      (libsource (lib "eagle-import") (part "mfpassives_RESISTOR_0603"))
    )
    (comp (ref "R12")
      (value "DNP")
      (footprint "eagle-import:R0603")
      (fields (field (name "POPULATE") "0"))
      (libsource (lib "eagle-import") (part "mfpassives_RESISTOR_0603"))
    )
    (comp (ref "R13")
      (value "2k")
      (footprint "eagle-import:R0402")
      (fields (field (name "HOUSEPART") "YES") (field (name "MPN") "MF-RES-0402-2K"))
      (libsource (lib "eagle-import") (part "mfpassives_RESISTOR_0402"))
    )
    (comp (ref "R14")
      (value "2k")
      (footprint "eagle-import:R0402")
      (fields (field (name "HOUSEPART") "YES") (field (name "MPN") "MF-RES-0402-2K"))
      (libsource (lib "eagle-import") (part "mfpassives_RESISTOR_0402"))
    )
    (comp (ref "R15")
      (value "22")
      (footprint "eagle-import:R0402_NOBORDER")
      (fields (field (name "HOUSEPART") "1") (field (name "MPN") "MF-RES-0402-22"))
      (libsource (lib "eagle-import") (part "RESISTOR_0402_NOBORDER"))
    )
    (comp (ref "R16")
      (value "22")
      (footprint "eagle-import:R0402_NOBORDER")
      (fields (field (name "HOUSEPART") "1") (field (name "MPN") "MF-RES-0402-22"))
      (libsource (lib "eagle-import") (part "RESISTOR_0402_NOBORDER"))
    )
    (comp (ref "R17")
      (value "22")
      (footprint "eagle-import:R0402_NOBORDER")
      (fields (field (name "HOUSEPART") "1") (field (name "MPN") "MF-RES-0402-22"))
      (libsource (lib "eagle-import") (part "RESISTOR_0402_NOBORDER"))
    )
    (comp (ref "R18")
      (value "DNP")
      (footprint "eagle-import:R0603")
      (fields (field (name "POPULATE") "0"))
      (libsource (lib "eagle-import") (part "mfpassives_RESISTOR_0603"))
    )
    (comp (ref "R19")
      (value "DNP")
      (footprint "eagle-import:R0603")
      (fields (field (name "POPULATE") "0"))
      (libsource (lib "eagle-import") (part "mfpassives_RESISTOR_0603"))
    )
    (comp (ref "R20")
      (value "DNP")
      (footprint "eagle-import:R0603")
      (fields (field (name "POPULATE") "0"))
      (libsource (lib "eagle-import") (part "mfpassives_RESISTOR_0603"))
    )
    (comp (ref "R21")
      (value "DNP")
      (footprint "eagle-import:R0603")
      (fields (field (name "POPULATE") "0"))
      (libsource (lib "eagle-import") (part "mfpassives_RESISTOR_0603"))
    )
    (comp (ref "RA")
      (value "0.5mOhm 1% 2W")
      (footprint "eagle-import:M1206")
      (fields (field (name "MF") "Stackpole Electronics") (field (name "MPN") "HCS1206FTL500"))
      (libsource (lib "eagle-import") (part "R-US_M1206"))
    )
    (comp (ref "RB")
      (value "0.5mOhm 1% 2W")
      (footprint "eagle-import:M1206")
      (fields (field (name "MF") "Stackpole Electronics") (field (name "MPN") "HCS1206FTL500"))
      (libsource (lib "eagle-import") (part "R-US_M1206"))
    )
    (comp (ref "RC")
      (value "0.5mOhm 1% 2W")
      (footprint "eagle-import:M1206")
      (fields (field (name "MF") "Stackpole Electronics") (field (name "MPN") "HCS1206FTL500"))
      (libsource (lib "eagle-import") (part "R-US_M1206"))
    )
    (comp (ref "SH1")
      (value "SHORTT5")
      (footprint "eagle-import:SHORT_TOP-50")
      (libsource (lib "eagle-import") (part "SHORTT5"))
    )
    (comp (ref "SH2")
      (value "SHORTT5")
      (footprint "eagle-import:SHORT_TOP-50")
      (libsource (lib "eagle-import") (part "SHORTT5"))
    )
    (comp (ref "SH3")
      (value "SHORTT5")
      (footprint "eagle-import:SHORT_TOP-50")
      (libsource (lib "eagle-import") (part "SHORTT5"))
    )
    (comp (ref "SH4")
      (value "SHORTMEDIUM")
      (footprint "eagle-import:SHORT_TOP-MEDIUM")
      (libsource (lib "eagle-import") (part "SHORTMEDIUM"))
    )
    (comp (ref "SWD")
      (value "JST-ZH6")
      (footprint "eagle-import:JST_S6B-ZR-SM4A-TF(LF)(SN)")
      (fields (field (name "MF") "JST") (field (name "MPN") "S6B-ZR-SM4A-TF(LF)(SN)"))
      (libsource (lib "eagle-import") (part "JST-ZH6"))
    )
    (comp (ref "TEMP1")
      (value "PAD24AWG_PAD")
      (footprint "eagle-import:24AWG_PAD")
      (libsource (lib "eagle-import") (part "PAD24AWG_PAD"))
    )
    (comp (ref "TEMP2")
      (value "PAD24AWG_PAD")
      (footprint "eagle-import:24AWG_PAD")
      (libsource (lib "eagle-import") (part "PAD24AWG_PAD"))
    )
    (comp (ref "U1")
      (value "STM32G474CEU6")
      (footprint "eagle-import:QFN50P700X700X60-49N")
      (fields (field (name "MOUSER_PART_NUMBER") "511-STM32G474CEU6"))
      (libsource (lib "eagle-import") (part "STM32G474CEU6"))
    )
    (comp (ref "U2")
      (value "TCAN334G")
      (footprint "eagle-import:SOIC8")
      (fields (field (name "MF") "TI") (field (name "MPN") "TCAN334GDCNT"))
      (libsource (lib "eagle-import") (part "TCAN334G"))
    )
    (comp (ref "U3")
      (value "AS5147")
      (footprint "eagle-import:TSSOP14")
      (fields (field (name "MF") "AMS") (field (name "MPN") "AS5047P-ATSM"))
      (libsource (lib "eagle-import") (part "AS5147"))
    )
    (comp (ref "U4")
      (value "MAX15062AATA+T")
      (footprint "eagle-import:21-0487A_MXM")
      (fields (field (name "COPYRIGHT") "Copyright (C) 2018 Accelerated Designs. All rights reserved"))
      (libsource (lib "eagle-import") (part "MAX15062AATA+T"))
    )
    (comp (ref "U5")
      (value "DRV8353S")
      (footprint "eagle-import:WQFN-40")
      (fields (field (name "MF") "TI") (field (name "MPN") "DRV8353FSRTAR"))
      (libsource (lib "eagle-import") (part "DRV8353S"))
    )
    (comp (ref "U6")
      (value "TCAN334GSOT23")
      (footprint "eagle-import:SOT23-8")
      (fields (field (name "MF") "TI") (field (name "MPN") "TCAN337GDR"))
      (libsource (lib "eagle-import") (part "TCAN334GSOT23"))
    )
  )
  (nets
    (net (code "1") (name "+3V3") (class "Default")
      (node (ref "ABS") (pin "1") (pinfunction "1_1") (pintype "passive"))
      (node (ref "C1") (pin "P$1") (pinfunction "P$1_P$1") (pintype "passive"))
      (node (ref "C10") (pin "P$1") (pinfunction "P$1_P$1") (pintype "passive"))
      (node (ref "C11") (pin "P$1") (pinfunction "P$1_P$1") (pintype "passive"))
      (node (ref "C12") (pin "P$1") (pinfunction "P$1_P$1") (pintype "passive"))
      (node (ref "C18") (pin "P$2") (pinfunction "P$2_P$2") (pintype "passive"))
      (node (ref "C2") (pin "P$1") (pinfunction "P$1_P$1") (pintype "passive"))
      (node (ref "C21") (pin "P$1") (pinfunction "P$1_P$1") (pintype "passive"))
      (node (ref "C4") (pin "P$1") (pinfunction "P$1_P$1") (pintype "passive"))
      (node (ref "C5") (pin "P$1") (pinfunction "P$1_P$1") (pintype "passive"))
      (node (ref "C56") (pin "P$1") (pinfunction "P$1_P$1") (pintype "passive"))
      (node (ref "C6") (pin "P$1") (pinfunction "P$1_P$1") (pintype "passive"))
      (node (ref "C7") (pin "P$2") (pinfunction "P$2_P$2") (pintype "passive"))
      (node (ref "C8") (pin "P$1") (pinfunction "P$1_P$1") (pintype "passive"))
      (node (ref "C9") (pin "P$1") (pinfunction "P$1_P$1") (pintype "passive"))
      (node (ref "D33") (pin "P$1") (pinfunction "P$1_P$1") (pintype "bidirectional"))
      (node (ref "ENC") (pin "1") (pinfunction "1_1") (pintype "passive"))
      (node (ref "L1") (pin "1") (pinfunction "1_1") (pintype "passive"))
      (node (ref "R1") (pin "P$1") (pinfunction "P$1_P$1") (pintype "passive"))
      (node (ref "R13") (pin "P$1") (pinfunction "P$1_P$1") (pintype "passive"))
      (node (ref "R14") (pin "P$1") (pinfunction "P$1_P$1") (pintype "passive"))
      (node (ref "R2") (pin "P$1") (pinfunction "P$1_P$1") (pintype "passive"))
      (node (ref "R3") (pin "P$1") (pinfunction "P$1_P$1") (pintype "passive"))
      (node (ref "R4") (pin "P$1") (pinfunction "P$1_P$1") (pintype "passive"))
      (node (ref "R8") (pin "P$1") (pinfunction "P$1_P$1") (pintype "passive"))
      (node (ref "SWD") (pin "6") (pinfunction "6_6") (pintype "passive"))
      (node (ref "TEMP1") (pin "P$1") (pinfunction "P$1_P$1") (pintype "bidirectional"))
      (node (ref "U1") (pin "1") (pinfunction "VBAT_1") (pintype "bidirectional"))
      (node (ref "U1") (pin "20") (pinfunction "VREF+_20") (pintype "bidirectional"))
      (node (ref "U1") (pin "21") (pinfunction "VDDA_21") (pintype "bidirectional"))
      (node (ref "U1") (pin "23") (pinfunction "VDD_1_23") (pintype "bidirectional"))
      (node (ref "U1") (pin "35") (pinfunction "VDD_2_35") (pintype "bidirectional"))
      (node (ref "U1") (pin "48") (pinfunction "VDD_3_48") (pintype "bidirectional"))
      (node (ref "U2") (pin "3") (pinfunction "VCC_3") (pintype "power_in"))
      (node (ref "U3") (pin "12") (pinfunction "VDD3V_12") (pintype "bidirectional"))
      (node (ref "U4") (pin "4") (pinfunction "FB/VOUT_4") (pintype "bidirectional"))
      (node (ref "U5") (pin "24") (pinfunction "VREF_24") (pintype "bidirectional"))
      (node (ref "U6") (pin "3") (pinfunction "VCC_3") (pintype "power_in"))
    )
    (net (code "2") (name "/AS5047_A") (class "Default")
      (node (ref "U1") (pin "43") (pinfunction "PB5_43") (pintype "bidirectional"))
      (node (ref "U3") (pin "7") (pinfunction "A_7") (pintype "bidirectional"))
    )
    (net (code "3") (name "/AS5047_B") (class "Default")
      (node (ref "U1") (pin "42") (pinfunction "PB4_42") (pintype "bidirectional"))
      (node (ref "U3") (pin "6") (pinfunction "B_6") (pintype "bidirectional"))
    )
    (net (code "4") (name "/AS5047_CS") (class "Default")
      (node (ref "U1") (pin "24") (pinfunction "PB11_24") (pintype "bidirectional"))
      (node (ref "U3") (pin "1") (pinfunction "CS/_1") (pintype "bidirectional"))
    )
    (net (code "5") (name "/AS5047_MISO") (class "Default")
      (node (ref "ENC") (pin "5") (pinfunction "5_5") (pintype "passive"))
      (node (ref "U1") (pin "27") (pinfunction "PB14_27") (pintype "bidirectional"))
      (node (ref "U3") (pin "3") (pinfunction "MISO_3") (pintype "bidirectional"))
    )
    (net (code "6") (name "/AS5047_MOSI") (class "Default")
      (node (ref "ENC") (pin "6") (pinfunction "6_6") (pintype "passive"))
      (node (ref "U1") (pin "28") (pinfunction "PB15_28") (pintype "bidirectional"))
      (node (ref "U3") (pin "4") (pinfunction "MOSI_4") (pintype "bidirectional"))
    )
    (net (code "7") (name "/AS5047_SCK") (class "Default")
      (node (ref "ENC") (pin "4") (pinfunction "4_4") (pintype "passive"))
      (node (ref "U1") (pin "26") (pinfunction "PB13_26") (pintype "bidirectional"))
      (node (ref "U3") (pin "2") (pinfunction "CLK_2") (pintype "bidirectional"))
    )
    (net (code "8") (name "/CAN2_N") (class "Default")
      (node (ref "L2") (pin "P$2") (pinfunction "2_P$2") (pintype "passive"))
      (node (ref "U2") (pin "6") (pinfunction "CANL_6") (pintype "bidirectional"))
      (node (ref "U6") (pin "6") (pinfunction "CANL_6") (pintype "bidirectional"))
    )
    (net (code "9") (name "/CAN2_P") (class "Default")
      (node (ref "L3") (pin "P$2") (pinfunction "2_P$2") (pintype "passive"))
      (node (ref "U2") (pin "7") (pinfunction "CANH_7") (pintype "bidirectional"))
      (node (ref "U6") (pin "7") (pinfunction "CANH_7") (pintype "bidirectional"))
    )
    (net (code "10") (name "/CAN_N") (class "Default")
      (node (ref "CAN1") (pin "2") (pinfunction "2_2") (pintype "passive"))
      (node (ref "CAN2") (pin "2") (pinfunction "2_2") (pintype "passive"))
      (node (ref "D4") (pin "2") (pinfunction "2_2") (pintype "bidirectional"))
      (node (ref "L2") (pin "P$1") (pinfunction "1_P$1") (pintype "passive"))
    )
    (net (code "11") (name "/CAN_P") (class "Default")
      (node (ref "CAN1") (pin "1") (pinfunction "1_1") (pintype "passive"))
      (node (ref "CAN2") (pin "1") (pinfunction "1_1") (pintype "passive"))
      (node (ref "D4") (pin "1") (pinfunction "1_1") (pintype "bidirectional"))
      (node (ref "L3") (pin "P$1") (pinfunction "1_P$1") (pintype "passive"))
    )
    (net (code "12") (name "/CAN_RX") (class "Default")
      (node (ref "U1") (pin "33") (pinfunction "PA11_33") (pintype "bidirectional"))
      (node (ref "U2") (pin "4") (pinfunction "RXD_4") (pintype "output"))
      (node (ref "U6") (pin "4") (pinfunction "RXD_4") (pintype "output"))
    )
    (net (code "13") (name "/CAN_TX") (class "Default")
      (node (ref "U1") (pin "34") (pinfunction "PA12_34") (pintype "bidirectional"))
      (node (ref "U2") (pin "1") (pinfunction "TXD_1") (pintype "input"))
      (node (ref "U6") (pin "1") (pinfunction "TXD_1") (pintype "input"))
    )
    (net (code "14") (name "/CUR1") (class "Default")
      (node (ref "R15") (pin "P$1") (pinfunction "P$1_P$1") (pintype "passive"))
      (node (ref "U5") (pin "23") (pinfunction "SOA_23") (pintype "bidirectional"))
    )
    (net (code "15") (name "/CUR2") (class "Default")
      (node (ref "R16") (pin "P$1") (pinfunction "P$1_P$1") (pintype "passive"))
      (node (ref "U5") (pin "22") (pinfunction "SOB_22") (pintype "bidirectional"))
    )
    (net (code "16") (name "/CUR3") (class "Default")
      (node (ref "R17") (pin "P$1") (pinfunction "P$1_P$1") (pintype "passive"))
      (node (ref "U5") (pin "21") (pinfunction "SOC_21") (pintype "bidirectional"))
    )
    (net (code "17") (name "/DAC") (class "Default")
      (node (ref "DAC") (pin "P$1") (pinfunction "P$1_P$1") (pintype "bidirectional"))
      (node (ref "U1") (pin "12") (pinfunction "PA4_12") (pintype "bidirectional"))
    )
    (net (code "18") (name "/DEBUG1") (class "Default")
      (node (ref "DBG1") (pin "P$1") (pinfunction "P$1_P$1") (pintype "bidirectional"))
      (node (ref "U1") (pin "3") (pinfunction "PC14-OSC32_IN_3") (pintype "bidirectional"))
    )
    (net (code "19") (name "/DEBUG2") (class "Default")
      (node (ref "DBG2") (pin "P$1") (pinfunction "P$1_P$1") (pintype "bidirectional"))
      (node (ref "U1") (pin "4") (pinfunction "PC15-OSC32_OUT_4") (pintype "bidirectional"))
    )
    (net (code "20") (name "/DEBUG_RX") (class "Default")
      (node (ref "DTR") (pin "P$1") (pinfunction "P$1_P$1") (pintype "bidirectional"))
      (node (ref "U1") (pin "40") (pinfunction "PC11_40") (pintype "bidirectional"))
    )
    (net (code "21") (name "/DEBUG_TX") (class "Default")
      (node (ref "DTX") (pin "P$1") (pinfunction "P$1_P$1") (pintype "bidirectional"))
      (node (ref "U1") (pin "39") (pinfunction "PC10_39") (pintype "bidirectional"))
    )
    (net (code "22") (name "/DRV8323_CS") (class "Default")
      (node (ref "DRV_CS") (pin "P$1") (pinfunction "P$1_P$1") (pintype "bidirectional"))
      (node (ref "U1") (pin "16") (pinfunction "PC4_16") (pintype "bidirectional"))
      (node (ref "U5") (pin "30") (pinfunction "CS_30") (pintype "bidirectional"))
    )
    (net (code "23") (name "/DRV8323_MISO") (class "Default")
      (node (ref "DRV_MISO") (pin "P$1") (pinfunction "P$1_P$1") (pintype "bidirectional"))
      (node (ref "R13") (pin "P$2") (pinfunction "P$2_P$2") (pintype "passive"))
      (node (ref "U1") (pin "14") (pinfunction "PA6_14") (pintype "bidirectional"))
      (node (ref "U5") (pin "27") (pinfunction "MISO_27") (pintype "bidirectional"))
    )
    (net (code "24") (name "/DRV8323_MOSI") (class "Default")
      (node (ref "DRV_MOSI") (pin "P$1") (pinfunction "P$1_P$1") (pintype "bidirectional"))
      (node (ref "U1") (pin "15") (pinfunction "PA7_15") (pintype "bidirectional"))
      (node (ref "U5") (pin "28") (pinfunction "MOSI_28") (pintype "bidirectional"))
    )
    (net (code "25") (name "/DRV8323_SCLK") (class "Default")
      (node (ref "DRV_SCK") (pin "P$1") (pinfunction "P$1_P$1") (pintype "bidirectional"))
      (node (ref "U1") (pin "13") (pinfunction "PA5_13") (pintype "bidirectional"))
      (node (ref "U5") (pin "29") (pinfunction "SCLK_29") (pintype "bidirectional"))
    )
    (net (code "26") (name "/FCUR1") (class "Default")
      (node (ref "C58") (pin "P$1") (pinfunction "P$1_P$1") (pintype "passive"))
      (node (ref "R15") (pin "P$2") (pinfunction "P$2_P$2") (pintype "passive"))
      (node (ref "U1") (pin "17") (pinfunction "PB0_17") (pintype "bidirectional"))
    )
    (net (code "27") (name "/FCUR2") (class "Default")
      (node (ref "C59") (pin "P$1") (pinfunction "P$1_P$1") (pintype "passive"))
      (node (ref "R16") (pin "P$2") (pinfunction "P$2_P$2") (pintype "passive"))
      (node (ref "U1") (pin "18") (pinfunction "PB1_18") (pintype "bidirectional"))
    )
    (net (code "28") (name "/FCUR3") (class "Default")
      (node (ref "C60") (pin "P$1") (pinfunction "P$1_P$1") (pintype "passive"))
      (node (ref "R17") (pin "P$2") (pinfunction "P$2_P$2") (pintype "passive"))
      (node (ref "U1") (pin "19") (pinfunction "PB2_19") (pintype "bidirectional"))
    )
    (net (code "29") (name "/GHA") (class "Default")
      (node (ref "Q1") (pin "4") (pinfunction "G_4") (pintype "passive"))
      (node (ref "U5") (pin "6") (pinfunction "GHA_6") (pintype "bidirectional"))
    )
    (net (code "30") (name "/GHB") (class "Default")
      (node (ref "Q3") (pin "4") (pinfunction "G_4") (pintype "passive"))
      (node (ref "U5") (pin "15") (pinfunction "GHB_15") (pintype "bidirectional"))
    )
    (net (code "31") (name "/GHC") (class "Default")
      (node (ref "Q5") (pin "4") (pinfunction "G_4") (pintype "passive"))
      (node (ref "U5") (pin "16") (pinfunction "GHC_16") (pintype "bidirectional"))
    )
    (net (code "32") (name "/GLA") (class "Default")
      (node (ref "Q2") (pin "4") (pinfunction "G_4") (pintype "passive"))
      (node (ref "U5") (pin "8") (pinfunction "GLA_8") (pintype "bidirectional"))
    )
    (net (code "33") (name "/GLB") (class "Default")
      (node (ref "Q4") (pin "4") (pinfunction "G_4") (pintype "passive"))
      (node (ref "U5") (pin "13") (pinfunction "GLB_13") (pintype "bidirectional"))
    )
    (net (code "34") (name "/GLC") (class "Default")
      (node (ref "Q6") (pin "4") (pinfunction "G_4") (pintype "passive"))
      (node (ref "U5") (pin "18") (pinfunction "GLC_18") (pintype "bidirectional"))
    )
    (net (code "35") (name "/I2C_ABS_SCL") (class "Default")
      (node (ref "ABS") (pin "2") (pinfunction "2_2") (pintype "passive"))
      (node (ref "R4") (pin "P$2") (pinfunction "P$2_P$2") (pintype "passive"))
      (node (ref "U1") (pin "46") (pinfunction "PB8-BOOT0_46") (pintype "bidirectional"))
    )
    (net (code "36") (name "/I2C_ABS_SDA") (class "Default")
      (node (ref "ABS") (pin "3") (pinfunction "3_3") (pintype "passive"))
      (node (ref "R3") (pin "P$2") (pinfunction "P$2_P$2") (pintype "passive"))
      (node (ref "U1") (pin "47") (pinfunction "PB9_47") (pintype "bidirectional"))
    )
    (net (code "37") (name "/LED1") (class "Default")
      (node (ref "D3") (pin "CATHODE") (pinfunction "CATHODE_CATHODE") (pintype "power_in"))
      (node (ref "U1") (pin "5") (pinfunction "PF0-OSC_IN_5") (pintype "bidirectional"))
    )
    (net (code "38") (name "/LED2") (class "Default")
      (node (ref "D2") (pin "CATHODE") (pinfunction "CATHODE_CATHODE") (pintype "power_in"))
      (node (ref "U1") (pin "6") (pinfunction "PF1-OSC_OUT_6") (pintype "bidirectional"))
    )
    (net (code "39") (name "/MOTOR1") (class "Default")
      (node (ref "MOT1") (pin "P$1") (pinfunction "P$1_P$1") (pintype "bidirectional"))
      (node (ref "U1") (pin "8") (pinfunction "PA0_8") (pintype "bidirectional"))
      (node (ref "U5") (pin "32") (pinfunction "INHA_32") (pintype "bidirectional"))
    )
    (net (code "40") (name "/MOTOR2") (class "Default")
      (node (ref "MOT2") (pin "P$1") (pinfunction "P$1_P$1") (pintype "bidirectional"))
      (node (ref "U1") (pin "9") (pinfunction "PA1_9") (pintype "bidirectional"))
      (node (ref "U5") (pin "34") (pinfunction "INHB_34") (pintype "bidirectional"))
    )
    (net (code "41") (name "/MOTOR3") (class "Default")
      (node (ref "MOT3") (pin "P$1") (pinfunction "P$1_P$1") (pintype "bidirectional"))
      (node (ref "U1") (pin "10") (pinfunction "PA2_10") (pintype "bidirectional"))
      (node (ref "U5") (pin "36") (pinfunction "INHC_36") (pintype "bidirectional"))
    )
    (net (code "42") (name "/MOTOR_ENABLE") (class "Default")
      (node (ref "U1") (pin "11") (pinfunction "PA3_11") (pintype "bidirectional"))
      (node (ref "U5") (pin "31") (pinfunction "ENABLE_31") (pintype "bidirectional"))
    )
    (net (code "43") (name "/MOTOR_FAULT") (class "Default")
      (node (ref "R14") (pin "P$2") (pinfunction "P$2_P$2") (pintype "passive"))
      (node (ref "U1") (pin "44") (pinfunction "PB6_44") (pintype "bidirectional"))
      (node (ref "U5") (pin "26") (pinfunction "FAULT_26") (pintype "bidirectional"))
    )
    (net (code "44") (name "/MOTOR_HIZ") (class "Default")
      (node (ref "U1") (pin "45") (pinfunction "PB7_45") (pintype "bidirectional"))
      (node (ref "U5") (pin "33") (pinfunction "INLA_33") (pintype "bidirectional"))
      (node (ref "U5") (pin "35") (pinfunction "INLB_35") (pintype "bidirectional"))
      (node (ref "U5") (pin "37") (pinfunction "INLC_37") (pintype "bidirectional"))
    )
    (net (code "45") (name "/NRST") (class "Default")
      (node (ref "C3") (pin "P$1") (pinfunction "P$1_P$1") (pintype "passive"))
      (node (ref "SWD") (pin "2") (pinfunction "2_2") (pintype "passive"))
      (node (ref "U1") (pin "7") (pinfunction "PG10-NRST_7") (pintype "bidirectional"))
    )
    (net (code "46") (name "/SECONDARY_ENC_CS") (class "Default")
      (node (ref "ENC") (pin "2") (pinfunction "2_2") (pintype "passive"))
      (node (ref "U1") (pin "2") (pinfunction "PC13_2") (pintype "bidirectional"))
    )
    (net (code "47") (name "/SHA") (class "Default")
      (node (ref "A") (pin "1") (pinfunction "P$1_1") (pintype "bidirectional"))
      (node (ref "C64") (pin "P$2") (pinfunction "P$2_P$2") (pintype "passive"))
      (node (ref "C65") (pin "P$1") (pinfunction "P$1_P$1") (pintype "passive"))
      (node (ref "DA") (pin "P$1") (pinfunction "P$1_P$1") (pintype "bidirectional"))
      (node (ref "Q1") (pin "1") (pinfunction "S_1") (pintype "passive"))
      (node (ref "Q1") (pin "2") (pinfunction "S_2") (pintype "passive"))
      (node (ref "Q1") (pin "3") (pinfunction "S_3") (pintype "passive"))
      (node (ref "Q2") (pin "5") (pinfunction "D_5") (pintype "passive"))
      (node (ref "Q2") (pin "6") (pinfunction "D_6") (pintype "passive"))
      (node (ref "Q2") (pin "7") (pinfunction "D_7") (pintype "passive"))
      (node (ref "Q2") (pin "8") (pinfunction "D_8") (pintype "passive"))
      (node (ref "Q2") (pin "PAD") (pinfunction "D_PAD") (pintype "passive"))
      (node (ref "U5") (pin "7") (pinfunction "SHA_7") (pintype "bidirectional"))
    )
    (net (code "48") (name "/SHB") (class "Default")
      (node (ref "B") (pin "1") (pinfunction "P$1_1") (pintype "bidirectional"))
      (node (ref "C66") (pin "P$2") (pinfunction "P$2_P$2") (pintype "passive"))
      (node (ref "C67") (pin "P$1") (pinfunction "P$1_P$1") (pintype "passive"))
      (node (ref "DB") (pin "P$1") (pinfunction "P$1_P$1") (pintype "bidirectional"))
      (node (ref "Q3") (pin "1") (pinfunction "S_1") (pintype "passive"))
      (node (ref "Q3") (pin "2") (pinfunction "S_2") (pintype "passive"))
      (node (ref "Q3") (pin "3") (pinfunction "S_3") (pintype "passive"))
      (node (ref "Q4") (pin "5") (pinfunction "D_5") (pintype "passive"))
      (node (ref "Q4") (pin "6") (pinfunction "D_6") (pintype "passive"))
      (node (ref "Q4") (pin "7") (pinfunction "D_7") (pintype "passive"))
      (node (ref "Q4") (pin "8") (pinfunction "D_8") (pintype "passive"))
      (node (ref "Q4") (pin "PAD") (pinfunction "D_PAD") (pintype "passive"))
      (node (ref "U5") (pin "14") (pinfunction "SHB_14") (pintype "bidirectional"))
    )
    (net (code "49") (name "/SHC") (class "Default")
      (node (ref "C") (pin "1") (pinfunction "P$1_1") (pintype "bidirectional"))
      (node (ref "C68") (pin "P$2") (pinfunction "P$2_P$2") (pintype "passive"))
      (node (ref "C69") (pin "P$1") (pinfunction "P$1_P$1") (pintype "passive"))
      (node (ref "DC") (pin "P$1") (pinfunction "P$1_P$1") (pintype "bidirectional"))
      (node (ref "Q5") (pin "1") (pinfunction "S_1") (pintype "passive"))
      (node (ref "Q5") (pin "2") (pinfunction "S_2") (pintype "passive"))
      (node (ref "Q5") (pin "3") (pinfunction "S_3") (pintype "passive"))
      (node (ref "Q6") (pin "5") (pinfunction "D_5") (pintype "passive"))
      (node (ref "Q6") (pin "6") (pinfunction "D_6") (pintype "passive"))
      (node (ref "Q6") (pin "7") (pinfunction "D_7") (pintype "passive"))
      (node (ref "Q6") (pin "8") (pinfunction "D_8") (pintype "passive"))
      (node (ref "Q6") (pin "PAD") (pinfunction "D_PAD") (pintype "passive"))
      (node (ref "U5") (pin "17") (pinfunction "SHC_17") (pintype "bidirectional"))
    )
    (net (code "50") (name "/SWCLK") (class "Default")
      (node (ref "SWD") (pin "5") (pinfunction "5_5") (pintype "passive"))
      (node (ref "U1") (pin "37") (pinfunction "PA14_37") (pintype "bidirectional"))
    )
    (net (code "51") (name "/SWDIO") (class "Default")
      (node (ref "SWD") (pin "3") (pinfunction "3_3") (pintype "passive"))
      (node (ref "U1") (pin "36") (pinfunction "PA13_36") (pintype "bidirectional"))
    )
    (net (code "52") (name "/SXA_N") (class "Default")
      (node (ref "SH1") (pin "1") (pinfunction "P$1_1") (pintype "bidirectional"))
      (node (ref "U5") (pin "10") (pinfunction "SNA_10") (pintype "bidirectional"))
    )
    (net (code "53") (name "/SXA_P") (class "Default")
      (node (ref "C61") (pin "P$2") (pinfunction "P$2_P$2") (pintype "passive"))
      (node (ref "Q2") (pin "1") (pinfunction "S_1") (pintype "passive"))
      (node (ref "Q2") (pin "2") (pinfunction "S_2") (pintype "passive"))
      (node (ref "Q2") (pin "3") (pinfunction "S_3") (pintype "passive"))
      (node (ref "R12") (pin "P$2") (pinfunction "P$2_P$2") (pintype "passive"))
      (node (ref "RA") (pin "2") (pinfunction "2_2") (pintype "passive"))
      (node (ref "U5") (pin "9") (pinfunction "SPA_9") (pintype "bidirectional"))
    )
    (net (code "54") (name "/SXB_N") (class "Default")
      (node (ref "SH2") (pin "1") (pinfunction "P$1_1") (pintype "bidirectional"))
      (node (ref "U5") (pin "11") (pinfunction "SNB_11") (pintype "bidirectional"))
    )
    (net (code "55") (name "/SXB_P") (class "Default")
      (node (ref "C62") (pin "P$2") (pinfunction "P$2_P$2") (pintype "passive"))
      (node (ref "Q4") (pin "1") (pinfunction "S_1") (pintype "passive"))
      (node (ref "Q4") (pin "2") (pinfunction "S_2") (pintype "passive"))
      (node (ref "Q4") (pin "3") (pinfunction "S_3") (pintype "passive"))
      (node (ref "R19") (pin "P$2") (pinfunction "P$2_P$2") (pintype "passive"))
      (node (ref "RB") (pin "2") (pinfunction "2_2") (pintype "passive"))
      (node (ref "U5") (pin "12") (pinfunction "SPB_12") (pintype "bidirectional"))
    )
    (net (code "56") (name "/SXC_N") (class "Default")
      (node (ref "SH3") (pin "1") (pinfunction "P$1_1") (pintype "bidirectional"))
      (node (ref "U5") (pin "20") (pinfunction "SNC_20") (pintype "bidirectional"))
    )
    (net (code "57") (name "/SXC_P") (class "Default")
      (node (ref "C63") (pin "P$2") (pinfunction "P$2_P$2") (pintype "passive"))
      (node (ref "Q6") (pin "1") (pinfunction "S_1") (pintype "passive"))
      (node (ref "Q6") (pin "2") (pinfunction "S_2") (pintype "passive"))
      (node (ref "Q6") (pin "3") (pinfunction "S_3") (pintype "passive"))
      (node (ref "R21") (pin "P$2") (pinfunction "P$2_P$2") (pintype "passive"))
      (node (ref "RC") (pin "2") (pinfunction "2_2") (pintype "passive"))
      (node (ref "U5") (pin "19") (pinfunction "SPC_19") (pintype "bidirectional"))
    )
    (net (code "58") (name "/VBAT_SENSE") (class "Default")
      (node (ref "C57") (pin "P$1") (pinfunction "P$1_P$1") (pintype "passive"))
      (node (ref "R5") (pin "P$1") (pinfunction "P$1_P$1") (pintype "passive"))
      (node (ref "R6") (pin "P$2") (pinfunction "P$2_P$2") (pintype "passive"))
      (node (ref "U1") (pin "25") (pinfunction "PB12_25") (pintype "bidirectional"))
    )
    (net (code "59") (name "/VSW") (class "Default")
      (node (ref "L1") (pin "2") (pinfunction "2_2") (pintype "passive"))
      (node (ref "U4") (pin "8") (pinfunction "LX_8") (pintype "passive"))
    )
    (net (code "60") (name "/VTEMP_FET") (class "Default")
      (node (ref "C13") (pin "P$1") (pinfunction "P$1_P$1") (pintype "passive"))
      (node (ref "R8") (pin "P$2") (pinfunction "P$2_P$2") (pintype "passive"))
      (node (ref "R9") (pin "P$1") (pinfunction "P$1_P$1") (pintype "passive"))
      (node (ref "U1") (pin "31") (pinfunction "PA9_31") (pintype "bidirectional"))
    )
    (net (code "61") (name "/VTEMP_MOT") (class "Default")
      (node (ref "R7") (pin "P$1") (pinfunction "P$1_P$1") (pintype "passive"))
      (node (ref "TEMP2") (pin "P$1") (pinfunction "P$1_P$1") (pintype "bidirectional"))
      (node (ref "U1") (pin "30") (pinfunction "PA8_30") (pintype "bidirectional"))
    )
    (net (code "62") (name "GND") (class "Default")
      (node (ref "ABS") (pin "4") (pinfunction "4_4") (pintype "passive"))
      (node (ref "C1") (pin "P$2") (pinfunction "P$2_P$2") (pintype "passive"))
      (node (ref "C10") (pin "P$2") (pinfunction "P$2_P$2") (pintype "passive"))
      (node (ref "C11") (pin "P$2") (pinfunction "P$2_P$2") (pintype "passive"))
      (node (ref "C12") (pin "P$2") (pinfunction "P$2_P$2") (pintype "passive"))
      (node (ref "C13") (pin "P$2") (pinfunction "P$2_P$2") (pintype "passive"))
      (node (ref "C18") (pin "P$1") (pinfunction "P$1_P$1") (pintype "passive"))
      (node (ref "C2") (pin "P$2") (pinfunction "P$2_P$2") (pintype "passive"))
      (node (ref "C20") (pin "P$2") (pinfunction "P$2_P$2") (pintype "passive"))
      (node (ref "C21") (pin "P$2") (pinfunction "P$2_P$2") (pintype "passive"))
      (node (ref "C3") (pin "P$2") (pinfunction "P$2_P$2") (pintype "passive"))
      (node (ref "C4") (pin "P$2") (pinfunction "P$2_P$2") (pintype "passive"))
      (node (ref "C5") (pin "P$2") (pinfunction "P$2_P$2") (pintype "passive"))
      (node (ref "C56") (pin "P$2") (pinfunction "P$2_P$2") (pintype "passive"))
      (node (ref "C57") (pin "P$2") (pinfunction "P$2_P$2") (pintype "passive"))
      (node (ref "C58") (pin "P$2") (pinfunction "P$2_P$2") (pintype "passive"))
      (node (ref "C59") (pin "P$2") (pinfunction "P$2_P$2") (pintype "passive"))
      (node (ref "C6") (pin "P$2") (pinfunction "P$2_P$2") (pintype "passive"))
      (node (ref "C60") (pin "P$2") (pinfunction "P$2_P$2") (pintype "passive"))
      (node (ref "C7") (pin "P$1") (pinfunction "P$1_P$1") (pintype "passive"))
      (node (ref "C8") (pin "P$2") (pinfunction "P$2_P$2") (pintype "passive"))
      (node (ref "C9") (pin "P$2") (pinfunction "P$2_P$2") (pintype "passive"))
      (node (ref "CAN1") (pin "3") (pinfunction "3_3") (pintype "passive"))
      (node (ref "CAN2") (pin "3") (pinfunction "3_3") (pintype "passive"))
      (node (ref "D4") (pin "3") (pinfunction "3_3") (pintype "bidirectional"))
      (node (ref "DG1") (pin "P$1") (pinfunction "P$1_P$1") (pintype "bidirectional"))
      (node (ref "DG2") (pin "P$1") (pinfunction "P$1_P$1") (pintype "bidirectional"))
      (node (ref "ENC") (pin "3") (pinfunction "3_3") (pintype "passive"))
      (node (ref "R6") (pin "P$1") (pinfunction "P$1_P$1") (pintype "passive"))
      (node (ref "R7") (pin "P$2") (pinfunction "P$2_P$2") (pintype "passive"))
      (node (ref "R9") (pin "P$2") (pinfunction "P$2_P$2") (pintype "passive"))
      (node (ref "SH4") (pin "2") (pinfunction "P$2_2") (pintype "bidirectional"))
      (node (ref "SWD") (pin "4") (pinfunction "4_4") (pintype "passive"))
      (node (ref "U1") (pin "38") (pinfunction "PA15_38") (pintype "bidirectional"))
      (node (ref "U1") (pin "49") (pinfunction "THERMALPAD_49") (pintype "bidirectional"))
      (node (ref "U2") (pin "2") (pinfunction "GND_2") (pintype "power_in"))
      (node (ref "U2") (pin "5") (pinfunction "SHDN_5") (pintype "input"))
      (node (ref "U2") (pin "8") (pinfunction "STB_8") (pintype "input"))
      (node (ref "U3") (pin "13") (pinfunction "GND_13") (pintype "bidirectional"))
      (node (ref "U3") (pin "5") (pinfunction "TEST_5") (pintype "bidirectional"))
      (node (ref "U4") (pin "7") (pinfunction "GND_7") (pintype "power_in"))
      (node (ref "U5") (pin "25") (pinfunction "AGND_25") (pintype "bidirectional"))
      (node (ref "U6") (pin "2") (pinfunction "GND_2") (pintype "power_in"))
      (node (ref "U6") (pin "5") (pinfunction "SHDN_5") (pintype "input"))
      (node (ref "U6") (pin "8") (pinfunction "STB_8") (pintype "input"))
    )
    (net (code "63") (name "Net-(C55-PadP$1)") (class "Default")
      (node (ref "C55") (pin "P$1") (pinfunction "P$1_P$1") (pintype "passive"))
      (node (ref "M3") (pin "P$1") (pinfunction "P$1_P$1") (pintype "bidirectional"))
      (node (ref "R10") (pin "P$1") (pinfunction "P$1_P$1") (pintype "passive"))
    )
    (net (code "64") (name "Net-(C64-PadP$1)") (class "Default")
      (node (ref "C64") (pin "P$1") (pinfunction "P$1_P$1") (pintype "passive"))
      (node (ref "R11") (pin "P$2") (pinfunction "P$2_P$2") (pintype "passive"))
    )
    (net (code "65") (name "Net-(C65-PadP$2)") (class "Default")
      (node (ref "C65") (pin "P$2") (pinfunction "P$2_P$2") (pintype "passive"))
      (node (ref "R12") (pin "P$1") (pinfunction "P$1_P$1") (pintype "passive"))
    )
    (net (code "66") (name "Net-(C66-PadP$1)") (class "Default")
      (node (ref "C66") (pin "P$1") (pinfunction "P$1_P$1") (pintype "passive"))
      (node (ref "R18") (pin "P$2") (pinfunction "P$2_P$2") (pintype "passive"))
    )
    (net (code "67") (name "Net-(C67-PadP$2)") (class "Default")
      (node (ref "C67") (pin "P$2") (pinfunction "P$2_P$2") (pintype "passive"))
      (node (ref "R19") (pin "P$1") (pinfunction "P$1_P$1") (pintype "passive"))
    )
    (net (code "68") (name "Net-(C68-PadP$1)") (class "Default")
      (node (ref "C68") (pin "P$1") (pinfunction "P$1_P$1") (pintype "passive"))
      (node (ref "R20") (pin "P$2") (pinfunction "P$2_P$2") (pintype "passive"))
    )
    (net (code "69") (name "Net-(C69-PadP$2)") (class "Default")
      (node (ref "C69") (pin "P$2") (pinfunction "P$2_P$2") (pintype "passive"))
      (node (ref "R21") (pin "P$1") (pinfunction "P$1_P$1") (pintype "passive"))
    )
    (net (code "70") (name "Net-(D2-PadANODE)") (class "Default")
      (node (ref "D2") (pin "ANODE") (pinfunction "ANODE_ANODE") (pintype "power_in"))
      (node (ref "R2") (pin "P$2") (pinfunction "P$2_P$2") (pintype "passive"))
    )
    (net (code "71") (name "Net-(D3-PadANODE)") (class "Default")
      (node (ref "D3") (pin "ANODE") (pinfunction "ANODE_ANODE") (pintype "power_in"))
      (node (ref "R1") (pin "P$2") (pinfunction "P$2_P$2") (pintype "passive"))
    )
    (net (code "72") (name "Net-(U4-VCC)") (class "Default")
      (node (ref "C20") (pin "P$1") (pinfunction "P$1_P$1") (pintype "passive"))
      (node (ref "U4") (pin "3") (pinfunction "VCC_3") (pintype "power_in"))
    )
    (net (code "73") (name "Net-(U5-CPH)") (class "Default")
      (node (ref "C16") (pin "P$1") (pinfunction "P$1_P$1") (pintype "passive"))
      (node (ref "U5") (pin "2") (pinfunction "CPH_2") (pintype "bidirectional"))
    )
    (net (code "74") (name "Net-(U5-CPL)") (class "Default")
      (node (ref "C16") (pin "P$2") (pinfunction "P$2_P$2") (pintype "passive"))
      (node (ref "U5") (pin "1") (pinfunction "CPL_1") (pintype "bidirectional"))
    )
    (net (code "75") (name "Net-(U5-DVDD)") (class "Default")
      (node (ref "C17") (pin "P$2") (pinfunction "P$2_P$2") (pintype "passive"))
      (node (ref "U5") (pin "38") (pinfunction "DVDD_38") (pintype "bidirectional"))
    )
    (net (code "76") (name "Net-(U5-VCP)") (class "Default")
      (node (ref "C15") (pin "P$2") (pinfunction "P$2_P$2") (pintype "passive"))
      (node (ref "U5") (pin "5") (pinfunction "VCP_5") (pintype "bidirectional"))
    )
    (net (code "77") (name "Net-(U5-VGLS)") (class "Default")
      (node (ref "C38") (pin "P$2") (pinfunction "P$2_P$2") (pintype "passive"))
      (node (ref "U5") (pin "40") (pinfunction "VGLS_40") (pintype "bidirectional"))
    )
    (net (code "78") (name "V+") (class "Default")
      (node (ref "C14") (pin "P$1") (pinfunction "P$1_P$1") (pintype "passive"))
      (node (ref "C15") (pin "P$1") (pinfunction "P$1_P$1") (pintype "passive"))
      (node (ref "C19") (pin "P$1") (pinfunction "P$1_P$1") (pintype "passive"))
      (node (ref "C22") (pin "P$1") (pinfunction "P$1_P$1") (pintype "passive"))
      (node (ref "C23") (pin "P$1") (pinfunction "P$1_P$1") (pintype "passive"))
      (node (ref "C24") (pin "P$1") (pinfunction "P$1_P$1") (pintype "passive"))
      (node (ref "C25") (pin "P$1") (pinfunction "P$1_P$1") (pintype "passive"))
      (node (ref "C26") (pin "P$1") (pinfunction "P$1_P$1") (pintype "passive"))
      (node (ref "C27") (pin "P$1") (pinfunction "P$1_P$1") (pintype "passive"))
      (node (ref "C28") (pin "P$1") (pinfunction "P$1_P$1") (pintype "passive"))
      (node (ref "C29") (pin "P$1") (pinfunction "P$1_P$1") (pintype "passive"))
      (node (ref "C30") (pin "P$1") (pinfunction "P$1_P$1") (pintype "passive"))
      (node (ref "C31") (pin "P$1") (pinfunction "P$1_P$1") (pintype "passive"))
      (node (ref "C32") (pin "P$1") (pinfunction "P$1_P$1") (pintype "passive"))
      (node (ref "C33") (pin "P$1") (pinfunction "P$1_P$1") (pintype "passive"))
      (node (ref "C34") (pin "P$1") (pinfunction "P$1_P$1") (pintype "passive"))
      (node (ref "C35") (pin "P$1") (pinfunction "P$1_P$1") (pintype "passive"))
      (node (ref "C36") (pin "P$1") (pinfunction "P$1_P$1") (pintype "passive"))
      (node (ref "C37") (pin "P$1") (pinfunction "P$1_P$1") (pintype "passive"))
      (node (ref "C39") (pin "P$1") (pinfunction "P$1_P$1") (pintype "passive"))
      (node (ref "C40") (pin "P$1") (pinfunction "P$1_P$1") (pintype "passive"))
      (node (ref "C41") (pin "P$1") (pinfunction "P$1_P$1") (pintype "passive"))
      (node (ref "C42") (pin "P$1") (pinfunction "P$1_P$1") (pintype "passive"))
      (node (ref "C43") (pin "P$1") (pinfunction "P$1_P$1") (pintype "passive"))
      (node (ref "C44") (pin "P$1") (pinfunction "P$1_P$1") (pintype "passive"))
      (node (ref "C45") (pin "P$1") (pinfunction "P$1_P$1") (pintype "passive"))
      (node (ref "C46") (pin "P$1") (pinfunction "P$1_P$1") (pintype "passive"))
      (node (ref "C47") (pin "P$1") (pinfunction "P$1_P$1") (pintype "passive"))
      (node (ref "C48") (pin "P$1") (pinfunction "P$1_P$1") (pintype "passive"))
      (node (ref "C49") (pin "P$1") (pinfunction "P$1_P$1") (pintype "passive"))
      (node (ref "C50") (pin "P$1") (pinfunction "P$1_P$1") (pintype "passive"))
      (node (ref "C51") (pin "P$1") (pinfunction "P$1_P$1") (pintype "passive"))
      (node (ref "C52") (pin "P$1") (pinfunction "P$1_P$1") (pintype "passive"))
      (node (ref "C53") (pin "P$1") (pinfunction "P$1_P$1") (pintype "passive"))
      (node (ref "C54") (pin "P$1") (pinfunction "P$1_P$1") (pintype "passive"))
      (node (ref "C61") (pin "P$1") (pinfunction "P$1_P$1") (pintype "passive"))
      (node (ref "C62") (pin "P$1") (pinfunction "P$1_P$1") (pintype "passive"))
      (node (ref "C63") (pin "P$1") (pinfunction "P$1_P$1") (pintype "passive"))
      (node (ref "J1") (pin "1") (pinfunction "1_1") (pintype "passive"))
      (node (ref "J2") (pin "1") (pinfunction "1_1") (pintype "passive"))
      (node (ref "Q1") (pin "5") (pinfunction "D_5") (pintype "passive"))
      (node (ref "Q1") (pin "6") (pinfunction "D_6") (pintype "passive"))
      (node (ref "Q1") (pin "7") (pinfunction "D_7") (pintype "passive"))
      (node (ref "Q1") (pin "8") (pinfunction "D_8") (pintype "passive"))
      (node (ref "Q1") (pin "PAD") (pinfunction "D_PAD") (pintype "passive"))
      (node (ref "Q3") (pin "5") (pinfunction "D_5") (pintype "passive"))
      (node (ref "Q3") (pin "6") (pinfunction "D_6") (pintype "passive"))
      (node (ref "Q3") (pin "7") (pinfunction "D_7") (pintype "passive"))
      (node (ref "Q3") (pin "8") (pinfunction "D_8") (pintype "passive"))
      (node (ref "Q3") (pin "PAD") (pinfunction "D_PAD") (pintype "passive"))
      (node (ref "Q5") (pin "5") (pinfunction "D_5") (pintype "passive"))
      (node (ref "Q5") (pin "6") (pinfunction "D_6") (pintype "passive"))
      (node (ref "Q5") (pin "7") (pinfunction "D_7") (pintype "passive"))
      (node (ref "Q5") (pin "8") (pinfunction "D_8") (pintype "passive"))
      (node (ref "Q5") (pin "PAD") (pinfunction "D_PAD") (pintype "passive"))
      (node (ref "R11") (pin "P$1") (pinfunction "P$1_P$1") (pintype "passive"))
      (node (ref "R18") (pin "P$1") (pinfunction "P$1_P$1") (pintype "passive"))
      (node (ref "R20") (pin "P$1") (pinfunction "P$1_P$1") (pintype "passive"))
      (node (ref "R5") (pin "P$2") (pinfunction "P$2_P$2") (pintype "passive"))
      (node (ref "U4") (pin "1") (pinfunction "VIN_1") (pintype "input"))
      (node (ref "U4") (pin "2") (pinfunction "EN/UVLO_2") (pintype "input"))
      (node (ref "U5") (pin "3") (pinfunction "VM_3") (pintype "bidirectional"))
      (node (ref "U5") (pin "4") (pinfunction "VDRAIN_4") (pintype "bidirectional"))
    )
    (net (code "79") (name "V-") (class "Default")
      (node (ref "C14") (pin "P$2") (pinfunction "P$2_P$2") (pintype "passive"))
      (node (ref "C17") (pin "P$1") (pinfunction "P$1_P$1") (pintype "passive"))
      (node (ref "C19") (pin "P$2") (pinfunction "P$2_P$2") (pintype "passive"))
      (node (ref "C22") (pin "P$2") (pinfunction "P$2_P$2") (pintype "passive"))
      (node (ref "C23") (pin "P$2") (pinfunction "P$2_P$2") (pintype "passive"))
      (node (ref "C24") (pin "P$2") (pinfunction "P$2_P$2") (pintype "passive"))
      (node (ref "C25") (pin "P$2") (pinfunction "P$2_P$2") (pintype "passive"))
      (node (ref "C26") (pin "P$2") (pinfunction "P$2_P$2") (pintype "passive"))
      (node (ref "C27") (pin "P$2") (pinfunction "P$2_P$2") (pintype "passive"))
      (node (ref "C28") (pin "P$2") (pinfunction "P$2_P$2") (pintype "passive"))
      (node (ref "C29") (pin "P$2") (pinfunction "P$2_P$2") (pintype "passive"))
      (node (ref "C30") (pin "P$2") (pinfunction "P$2_P$2") (pintype "passive"))
      (node (ref "C31") (pin "P$2") (pinfunction "P$2_P$2") (pintype "passive"))
      (node (ref "C32") (pin "P$2") (pinfunction "P$2_P$2") (pintype "passive"))
      (node (ref "C33") (pin "P$2") (pinfunction "P$2_P$2") (pintype "passive"))
      (node (ref "C34") (pin "P$2") (pinfunction "P$2_P$2") (pintype "passive"))
      (node (ref "C35") (pin "P$2") (pinfunction "P$2_P$2") (pintype "passive"))
      (node (ref "C36") (pin "P$2") (pinfunction "P$2_P$2") (pintype "passive"))
      (node (ref "C37") (pin "P$2") (pinfunction "P$2_P$2") (pintype "passive"))
      (node (ref "C38") (pin "P$1") (pinfunction "P$1_P$1") (pintype "passive"))
      (node (ref "C39") (pin "P$2") (pinfunction "P$2_P$2") (pintype "passive"))
      (node (ref "C40") (pin "P$2") (pinfunction "P$2_P$2") (pintype "passive"))
      (node (ref "C41") (pin "P$2") (pinfunction "P$2_P$2") (pintype "passive"))
      (node (ref "C42") (pin "P$2") (pinfunction "P$2_P$2") (pintype "passive"))
      (node (ref "C43") (pin "P$2") (pinfunction "P$2_P$2") (pintype "passive"))
      (node (ref "C44") (pin "P$2") (pinfunction "P$2_P$2") (pintype "passive"))
      (node (ref "C45") (pin "P$2") (pinfunction "P$2_P$2") (pintype "passive"))
      (node (ref "C46") (pin "P$2") (pinfunction "P$2_P$2") (pintype "passive"))
      (node (ref "C47") (pin "P$2") (pinfunction "P$2_P$2") (pintype "passive"))
      (node (ref "C48") (pin "P$2") (pinfunction "P$2_P$2") (pintype "passive"))
      (node (ref "C49") (pin "P$2") (pinfunction "P$2_P$2") (pintype "passive"))
      (node (ref "C50") (pin "P$2") (pinfunction "P$2_P$2") (pintype "passive"))
      (node (ref "C51") (pin "P$2") (pinfunction "P$2_P$2") (pintype "passive"))
      (node (ref "C52") (pin "P$2") (pinfunction "P$2_P$2") (pintype "passive"))
      (node (ref "C53") (pin "P$2") (pinfunction "P$2_P$2") (pintype "passive"))
      (node (ref "C54") (pin "P$2") (pinfunction "P$2_P$2") (pintype "passive"))
      (node (ref "C55") (pin "P$2") (pinfunction "P$2_P$2") (pintype "passive"))
      (node (ref "J1") (pin "2") (pinfunction "2_2") (pintype "passive"))
      (node (ref "J2") (pin "2") (pinfunction "2_2") (pintype "passive"))
      (node (ref "R10") (pin "P$2") (pinfunction "P$2_P$2") (pintype "passive"))
      (node (ref "RA") (pin "1") (pinfunction "1_1") (pintype "passive"))
      (node (ref "RB") (pin "1") (pinfunction "1_1") (pintype "passive"))
      (node (ref "RC") (pin "1") (pinfunction "1_1") (pintype "passive"))
      (node (ref "SH1") (pin "2") (pinfunction "P$2_2") (pintype "bidirectional"))
      (node (ref "SH2") (pin "2") (pinfunction "P$2_2") (pintype "bidirectional"))
      (node (ref "SH3") (pin "2") (pinfunction "P$2_2") (pintype "bidirectional"))
      (node (ref "SH4") (pin "1") (pinfunction "P$1_1") (pintype "bidirectional"))
      (node (ref "U5") (pin "39") (pinfunction "GND_39") (pintype "bidirectional"))
      (node (ref "U5") (pin "P1") (pinfunction "PAD_P1") (pintype "bidirectional"))
      (node (ref "U5") (pin "P12") (pinfunction "PAD_P12") (pintype "bidirectional"))
      (node (ref "U5") (pin "P13") (pinfunction "PAD_P13") (pintype "bidirectional"))
      (node (ref "U5") (pin "P14") (pinfunction "PAD_P14") (pintype "bidirectional"))
      (node (ref "U5") (pin "P17") (pinfunction "PAD_P17") (pintype "bidirectional"))
      (node (ref "U5") (pin "P18") (pinfunction "PAD_P18") (pintype "bidirectional"))
      (node (ref "U5") (pin "P19") (pinfunction "PAD_P19") (pintype "bidirectional"))
      (node (ref "U5") (pin "P2") (pinfunction "PAD_P2") (pintype "bidirectional"))
      (node (ref "U5") (pin "P3") (pinfunction "PAD_P3") (pintype "bidirectional"))
      (node (ref "U5") (pin "P7") (pinfunction "PAD_P7") (pintype "bidirectional"))
      (node (ref "U5") (pin "P8") (pinfunction "PAD_P8") (pintype "bidirectional"))
      (node (ref "U5") (pin "P9") (pinfunction "PAD_P9") (pintype "bidirectional"))
      (node (ref "U5") (pin "PAD") (pinfunction "PAD_PAD") (pintype "bidirectional"))
    )
    (net (code "80") (name "unconnected-(M1-PadP$1)") (class "Default")
      (node (ref "M1") (pin "P$1") (pinfunction "P$1_P$1") (pintype "bidirectional"))
    )
    (net (code "81") (name "unconnected-(M2-PadP$1)") (class "Default")
      (node (ref "M2") (pin "P$1") (pinfunction "P$1_P$1") (pintype "bidirectional"))
    )
    (net (code "82") (name "unconnected-(M4-PadP$1)") (class "Default")
      (node (ref "M4") (pin "P$1") (pinfunction "P$1_P$1") (pintype "bidirectional"))
    )
    (net (code "83") (name "unconnected-(SWD-Pad1)") (class "Default")
      (node (ref "SWD") (pin "1") (pinfunction "1_1") (pintype "passive"))
    )
    (net (code "84") (name "unconnected-(U1-PA10-Pad32)") (class "Default")
      (node (ref "U1") (pin "32") (pinfunction "PA10_32") (pintype "bidirectional"))
    )
    (net (code "85") (name "unconnected-(U1-PB3-Pad41)") (class "Default")
      (node (ref "U1") (pin "41") (pinfunction "PB3_41") (pintype "bidirectional"))
    )
    (net (code "86") (name "unconnected-(U1-PB10-Pad22)") (class "Default")
      (node (ref "U1") (pin "22") (pinfunction "PB10_22") (pintype "bidirectional"))
    )
    (net (code "87") (name "unconnected-(U1-PC6-Pad29)") (class "Default")
      (node (ref "U1") (pin "29") (pinfunction "PC6_29") (pintype "bidirectional"))
    )
    (net (code "88") (name "unconnected-(U3-I-Pad14)") (class "Default")
      (node (ref "U3") (pin "14") (pinfunction "I_14") (pintype "bidirectional"))
    )
    (net (code "89") (name "unconnected-(U3-PWM-Pad8)") (class "Default")
      (node (ref "U3") (pin "8") (pinfunction "PWM_8") (pintype "bidirectional"))
    )
    (net (code "90") (name "unconnected-(U3-VDD5V-Pad11)") (class "Default")
      (node (ref "U3") (pin "11") (pinfunction "VDD5V_11") (pintype "bidirectional"))
    )
    (net (code "91") (name "unconnected-(U4-MODE-Pad5)") (class "Default")
      (node (ref "U4") (pin "5") (pinfunction "MODE_5") (pintype "input"))
    )
    (net (code "92") (name "unconnected-(U4-~{RESET}-Pad6)") (class "Default")
      (node (ref "U4") (pin "6") (pinfunction "~{RESET}_6") (pintype "output"))
    )
  )
)
